# controller.net
KiCad netlist of a schematic drawn in EAGLE
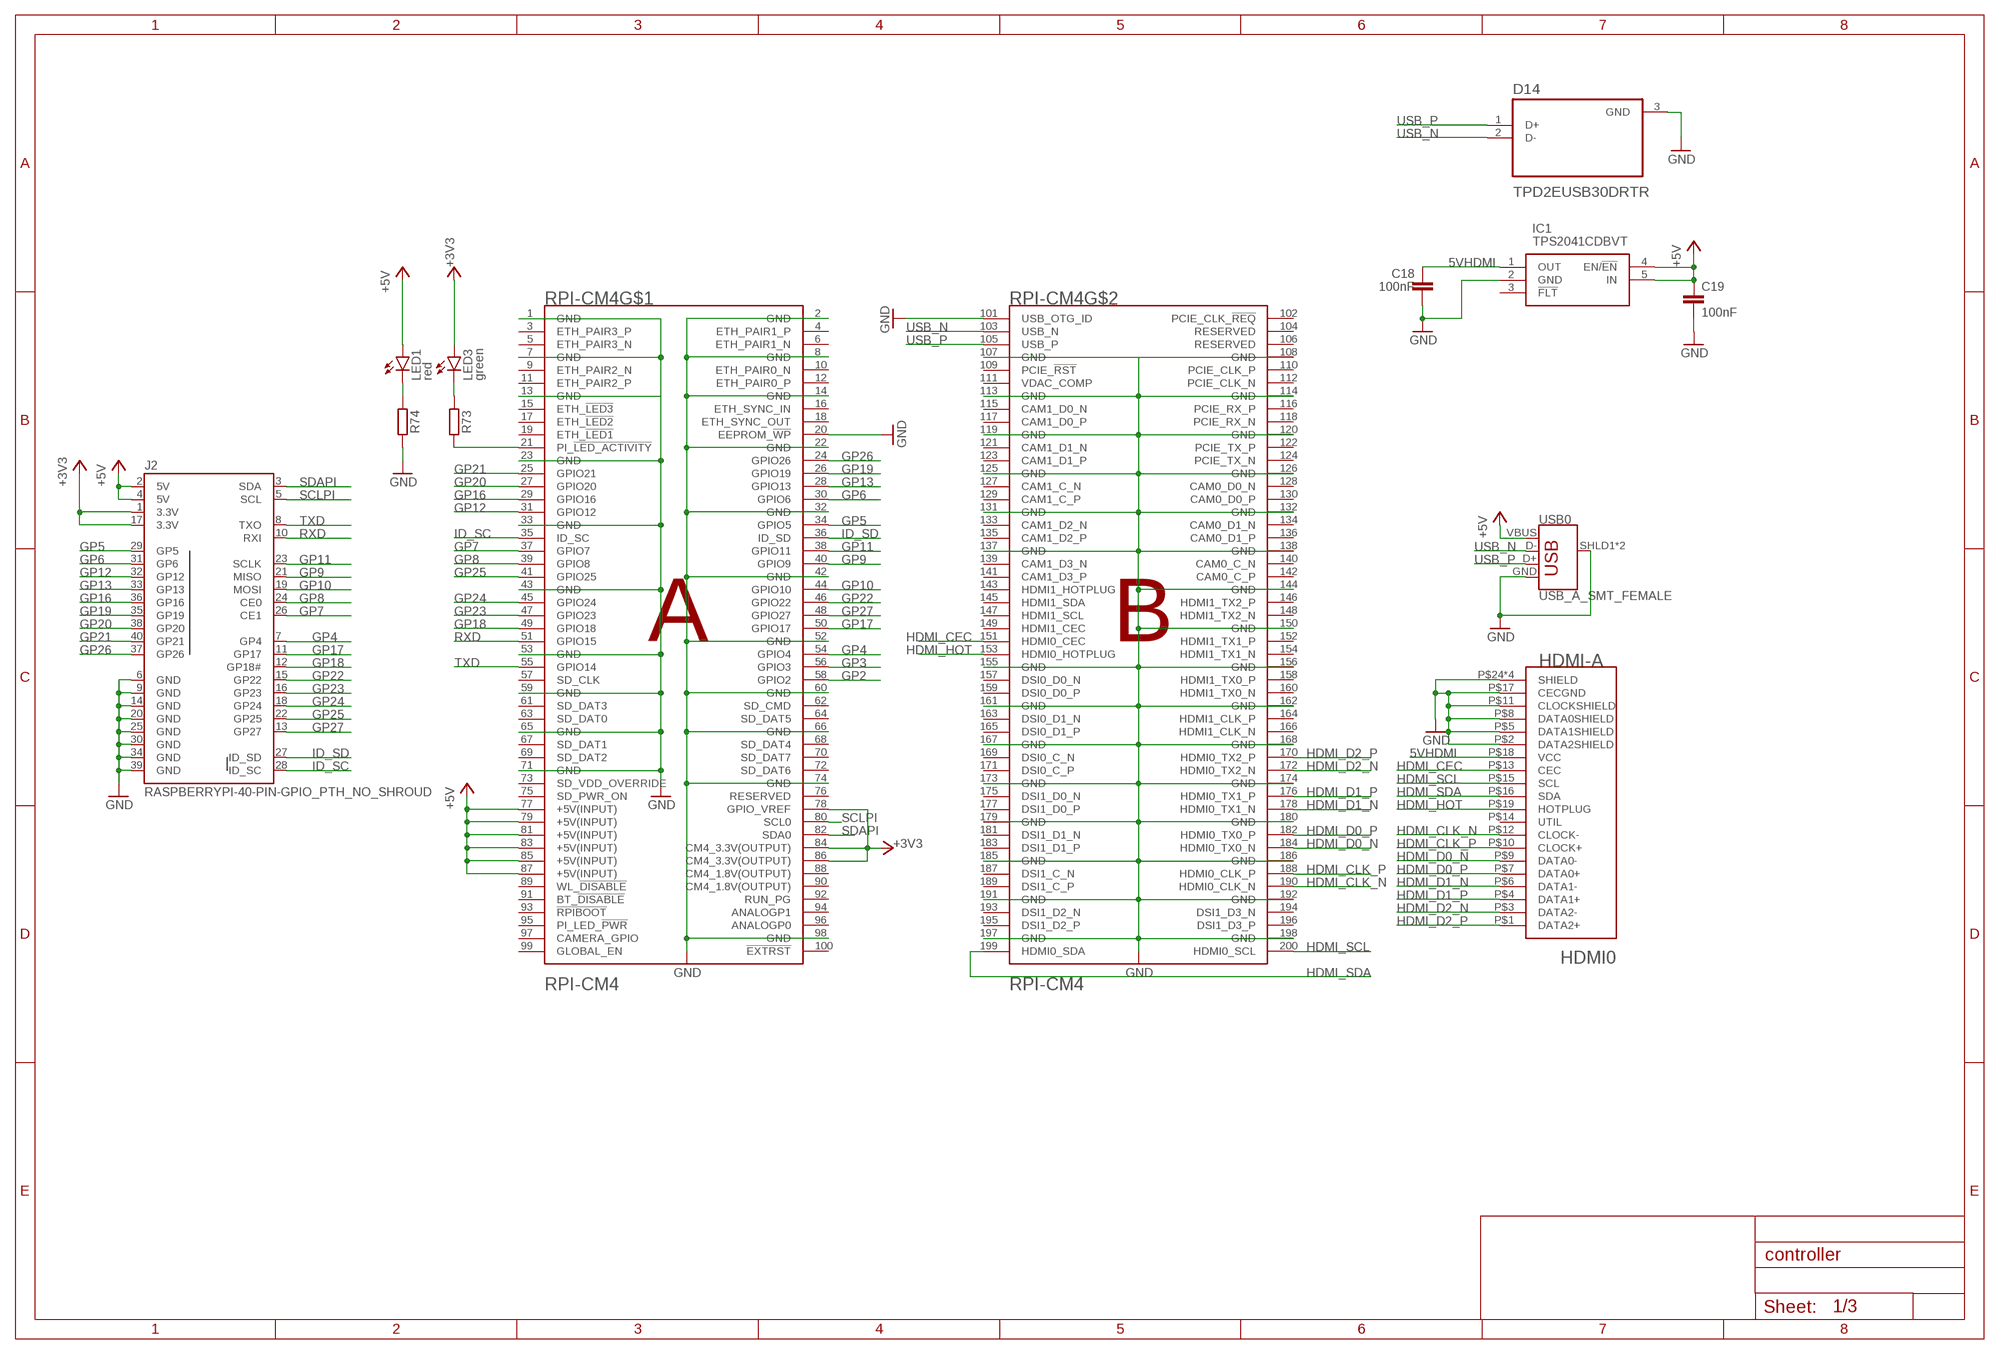
[diagram p0: schematic, sheet 1]
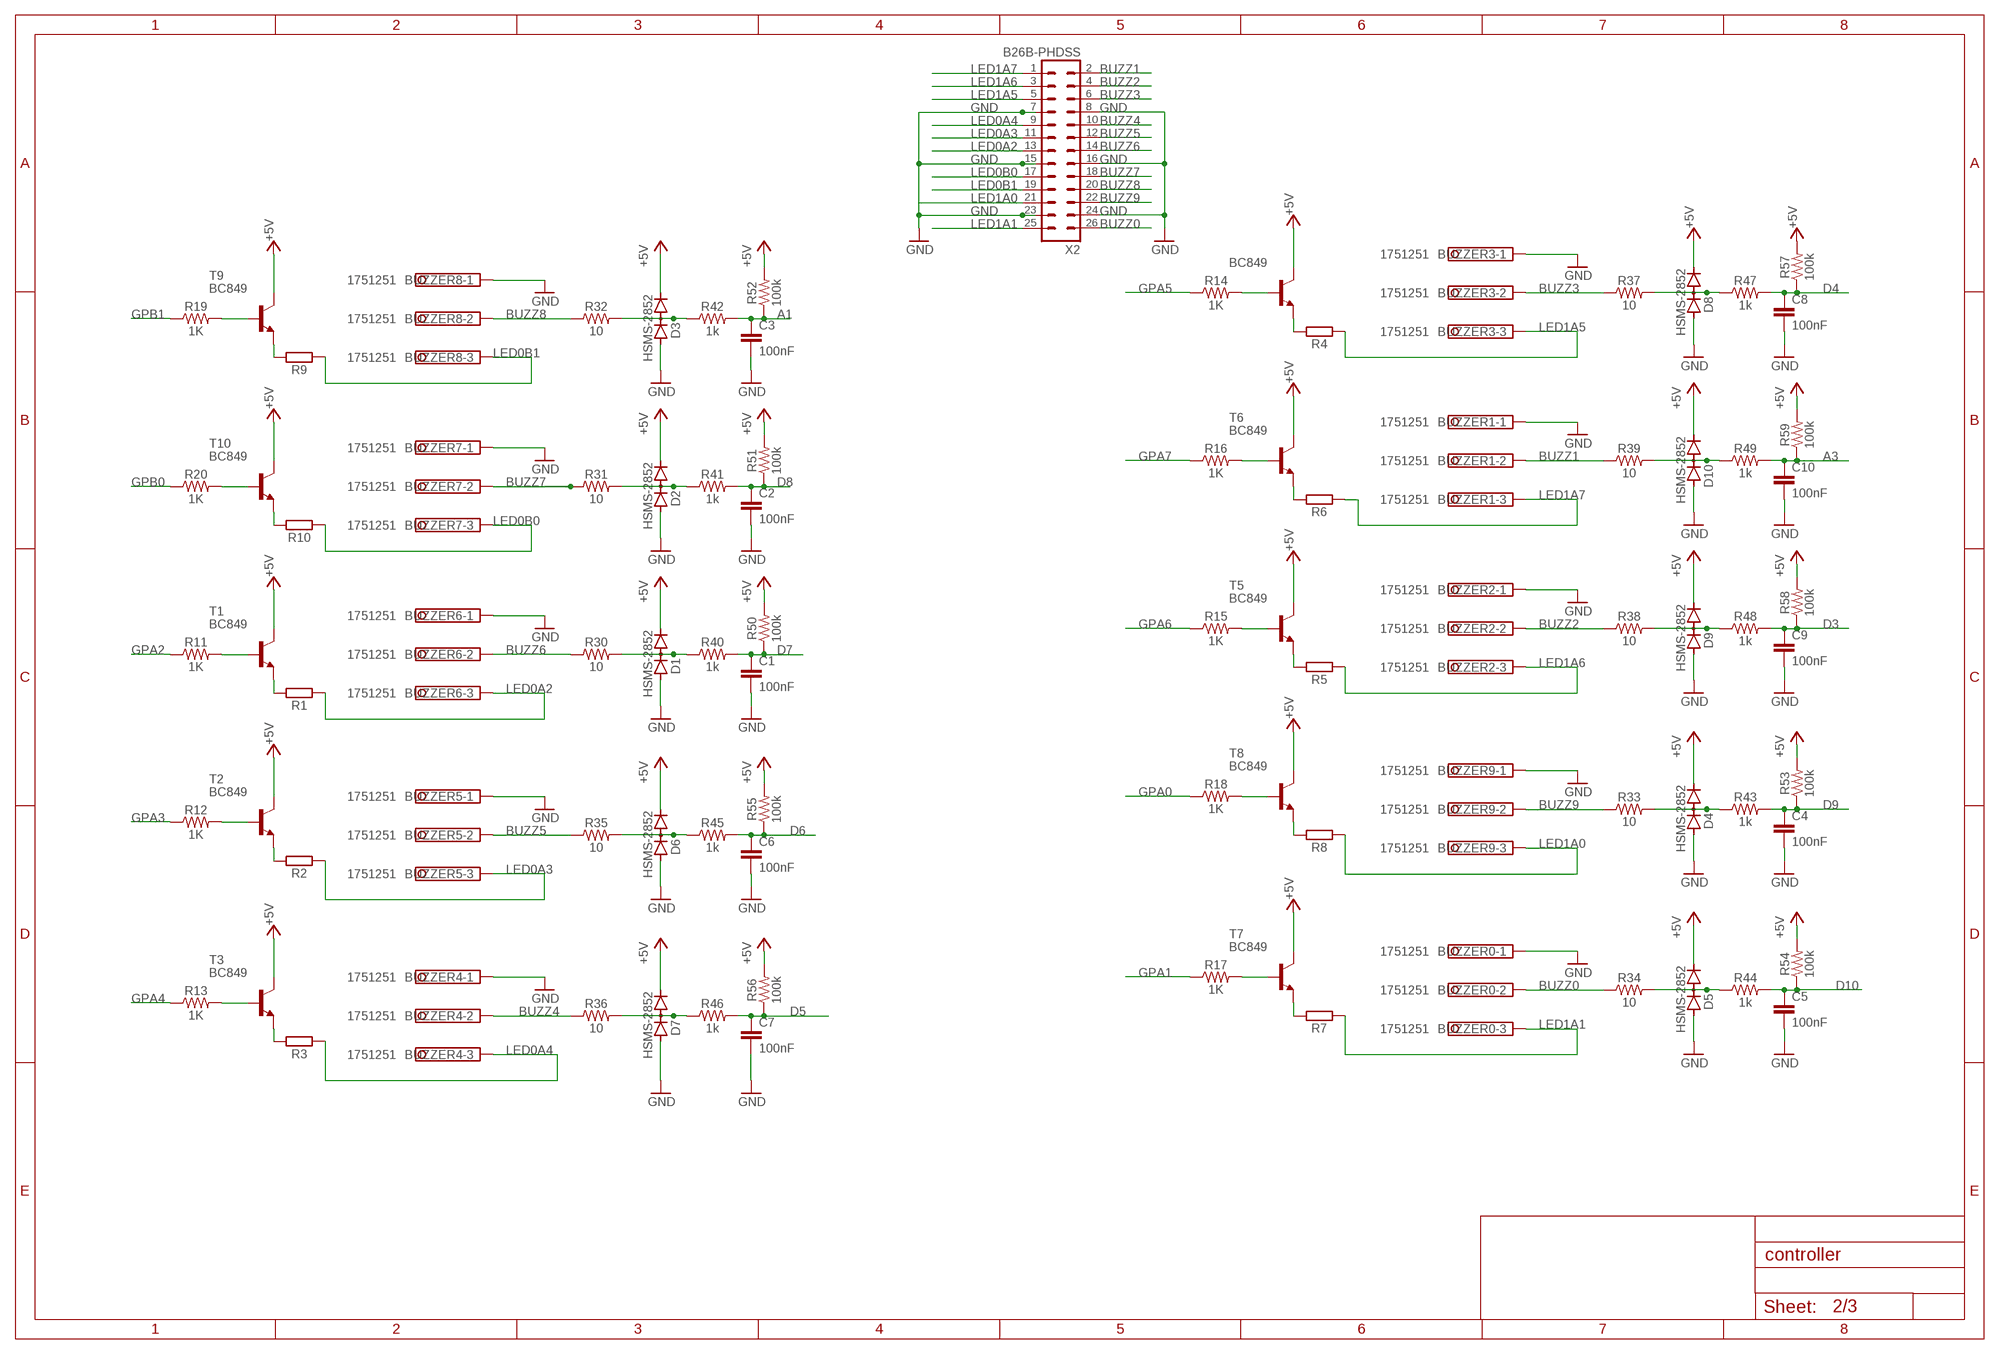
[diagram p1: schematic, sheet 2]
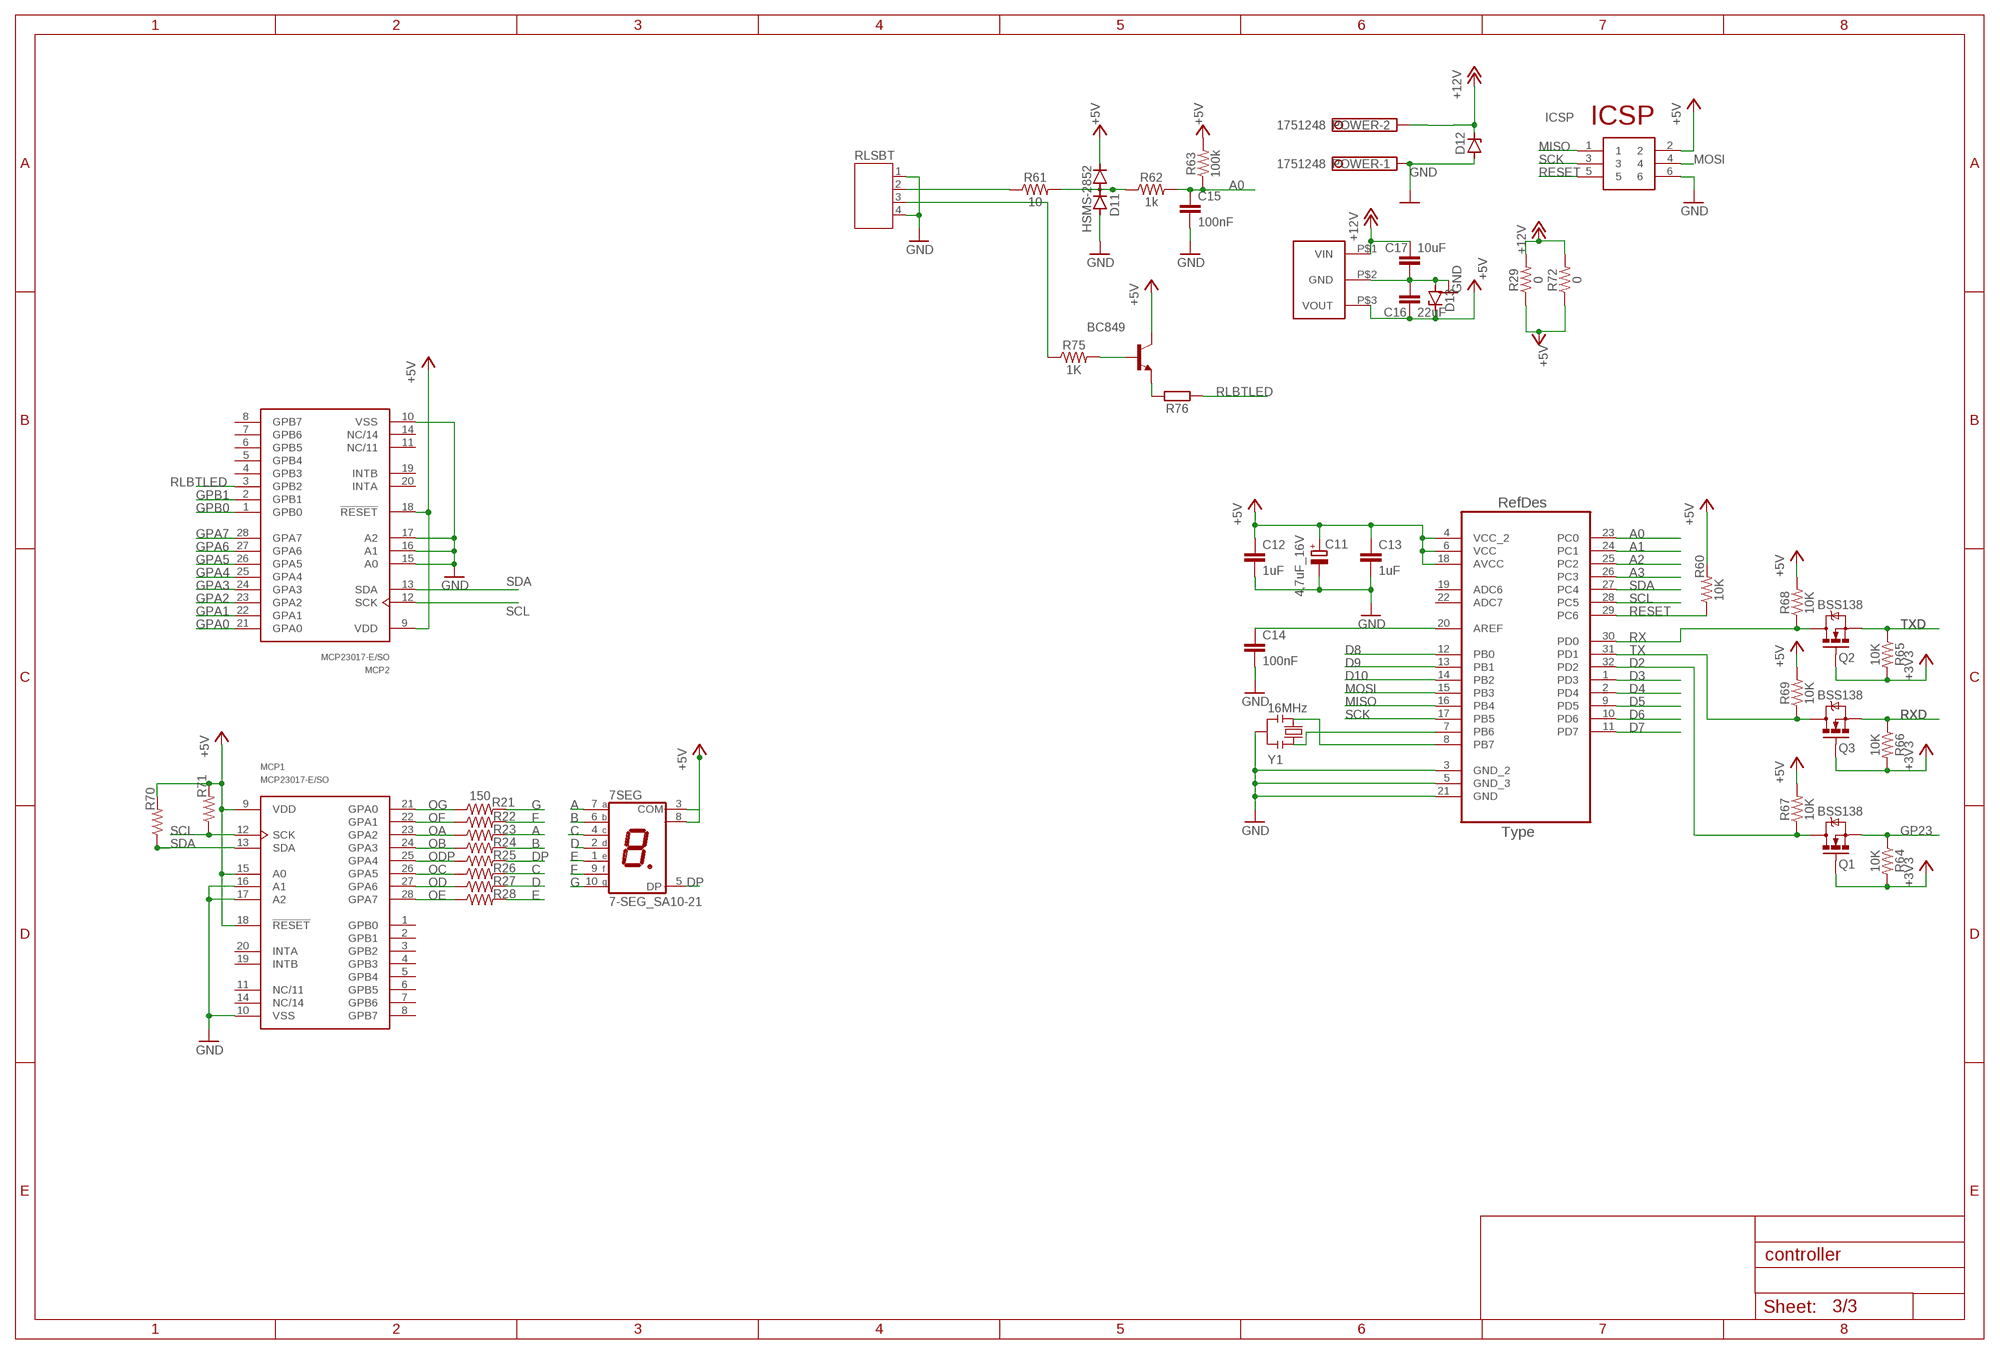
[diagram p2: schematic, sheet 3]

(export (version "E")
  (design (tool "Eeschema 10.0.6"))
  (components
    (comp (ref "7SEG")
      (value "7-SEG_SA10-21")
      (footprint "eagle-import:SA10-21")
      (libsource (lib "eagle-import") (part "7-SEG_SA10-21"))
    )
    (comp (ref "C11")
      (value "4,7uF_16V")
      (footprint "eagle-import:TAN-A")
      (fields (field (name "PART_NUMBER") "TAJA475MO16RNJ"))
      (libsource (lib "eagle-import") (part "0833_TAJA475MO16RNJ"))
    )
    (comp (ref "C12")
      (value "1uF")
      (footprint "eagle-import:C0603-ROUND")
      (fields (field (name "PART_NUMBER") "1uF_0603/GRM188R61E105KA12D"))
      (libsource (lib "eagle-import") (part "0006_1UF_0603/GRM188R61E105KA12D"))
    )
    (comp (ref "C13")
      (value "1uF")
      (footprint "eagle-import:C0603-ROUND")
      (fields (field (name "PART_NUMBER") "1uF_0603/GRM188R61E105KA12D"))
      (libsource (lib "eagle-import") (part "0006_1UF_0603/GRM188R61E105KA12D"))
    )
    (comp (ref "C14")
      (value "100nF")
      (footprint "eagle-import:C0603-ROUND")
      (fields (field (name "PART_NUMBER") "cl10b104kbnc"))
      (libsource (lib "eagle-import") (part "0015_100NF_0603"))
    )
    (comp (ref "C15")
      (value "100nF")
      (footprint "eagle-import:C0805")
      (libsource (lib "eagle-import") (part "C-EUC0805"))
    )
    (comp (ref "C16")
      (value "22uF")
      (footprint "eagle-import:C0805")
      (libsource (lib "eagle-import") (part "C-EUC0805"))
    )
    (comp (ref "C17")
      (value "10uF")
      (footprint "eagle-import:C0805")
      (libsource (lib "eagle-import") (part "C-EUC0805"))
    )
    (comp (ref "D11")
      (value "HSMS-2852")
      (footprint "eagle-import:SOT23")
      (libsource (lib "eagle-import") (part "HSMS-2852"))
    )
    (comp (ref "D12")
      (value "ZENER-DIODESMB")
      (footprint "eagle-import:SMB")
      (libsource (lib "eagle-import") (part "ZENER-DIODESMB"))
    )
    (comp (ref "D13")
      (value "ZENER-DIODESMB")
      (footprint "eagle-import:SMB")
      (libsource (lib "eagle-import") (part "ZENER-DIODESMB"))
    )
    (comp (ref "ICSP")
      (value "61200621621")
      (footprint "eagle-import:SHDR6W64P254_2X3_1528X910X910P")
      (fields (field (name "MOUSER_PART_NUMBER") "710-61200621621"))
      (libsource (lib "eagle-import") (part "61200621621"))
    )
    (comp (ref "MCP1")
      (value "MCP23017-E/SO")
      (footprint "eagle-import:SOIC28")
      (libsource (lib "eagle-import") (part "MCP23017-E/SO"))
    )
    (comp (ref "MCP2")
      (value "MCP23017-E/SO")
      (footprint "eagle-import:SOIC28")
      (libsource (lib "eagle-import") (part "MCP23017-E/SO"))
    )
    (comp (ref "POWER")
      (value "1751248")
      (footprint "eagle-import:1751248")
      (libsource (lib "eagle-import") (part "1751248"))
    )
    (comp (ref "Q1")
      (value "BSS138")
      (footprint "eagle-import:SOT23-3")
      (libsource (lib "eagle-import") (part "MOSFET-NCHANNELSMD"))
    )
    (comp (ref "Q2")
      (value "BSS138")
      (footprint "eagle-import:SOT23-3")
      (libsource (lib "eagle-import") (part "MOSFET-NCHANNELSMD"))
    )
    (comp (ref "Q3")
      (value "BSS138")
      (footprint "eagle-import:SOT23-3")
      (libsource (lib "eagle-import") (part "MOSFET-NCHANNELSMD"))
    )
    (comp (ref "R21")
      (value "150")
      (footprint "eagle-import:0805")
      (libsource (lib "eagle-import") (part "RESISTOR0805"))
    )
    (comp (ref "R22")
      (value "150")
      (footprint "eagle-import:0805")
      (libsource (lib "eagle-import") (part "RESISTOR0805"))
    )
    (comp (ref "R23")
      (value "150")
      (footprint "eagle-import:0805")
      (libsource (lib "eagle-import") (part "RESISTOR0805"))
    )
    (comp (ref "R24")
      (value "150")
      (footprint "eagle-import:0805")
      (libsource (lib "eagle-import") (part "RESISTOR0805"))
    )
    (comp (ref "R25")
      (value "150")
      (footprint "eagle-import:0805")
      (libsource (lib "eagle-import") (part "RESISTOR0805"))
    )
    (comp (ref "R26")
      (value "150")
      (footprint "eagle-import:0805")
      (libsource (lib "eagle-import") (part "RESISTOR0805"))
    )
    (comp (ref "R27")
      (value "150")
      (footprint "eagle-import:0805")
      (libsource (lib "eagle-import") (part "RESISTOR0805"))
    )
    (comp (ref "R28")
      (value "150")
      (footprint "eagle-import:0805")
      (libsource (lib "eagle-import") (part "RESISTOR0805"))
    )
    (comp (ref "R29")
      (value "0")
      (footprint "eagle-import:0805")
      (libsource (lib "eagle-import") (part "RESISTOR0805"))
    )
    (comp (ref "R60")
      (value "10K")
      (footprint "eagle-import:0805")
      (libsource (lib "eagle-import") (part "RESISTOR0805"))
    )
    (comp (ref "R61")
      (value "10")
      (footprint "eagle-import:0805")
      (libsource (lib "eagle-import") (part "RESISTOR0805"))
    )
    (comp (ref "R62")
      (value "1k")
      (footprint "eagle-import:0805")
      (libsource (lib "eagle-import") (part "RESISTOR0805"))
    )
    (comp (ref "R63")
      (value "100k")
      (footprint "eagle-import:0805")
      (libsource (lib "eagle-import") (part "RESISTOR0805"))
    )
    (comp (ref "R64")
      (value "10K")
      (footprint "eagle-import:0805")
      (libsource (lib "eagle-import") (part "RESISTOR0805"))
    )
    (comp (ref "R65")
      (value "10K")
      (footprint "eagle-import:0805")
      (libsource (lib "eagle-import") (part "RESISTOR0805"))
    )
    (comp (ref "R66")
      (value "10K")
      (footprint "eagle-import:0805")
      (libsource (lib "eagle-import") (part "RESISTOR0805"))
    )
    (comp (ref "R67")
      (value "10K")
      (footprint "eagle-import:0805")
      (libsource (lib "eagle-import") (part "RESISTOR0805"))
    )
    (comp (ref "R68")
      (value "10K")
      (footprint "eagle-import:0805")
      (libsource (lib "eagle-import") (part "RESISTOR0805"))
    )
    (comp (ref "R69")
      (value "10K")
      (footprint "eagle-import:0805")
      (libsource (lib "eagle-import") (part "RESISTOR0805"))
    )
    (comp (ref "R70")
      (value "RESISTOR0805")
      (footprint "eagle-import:0805")
      (libsource (lib "eagle-import") (part "RESISTOR0805"))
    )
    (comp (ref "R71")
      (value "RESISTOR0805")
      (footprint "eagle-import:0805")
      (libsource (lib "eagle-import") (part "RESISTOR0805"))
    )
    (comp (ref "R72")
      (value "0")
      (footprint "eagle-import:0805")
      (libsource (lib "eagle-import") (part "RESISTOR0805"))
    )
    (comp (ref "R75")
      (value "1K")
      (footprint "eagle-import:0805")
      (libsource (lib "eagle-import") (part "RESISTOR0805"))
    )
    (comp (ref "R76")
      (value "50")
      (footprint "eagle-import:R2512")
      (libsource (lib "eagle-import") (part "R-EU_R2512"))
    )
    (comp (ref "RLSBT")
      (value "JST-PH4")
      (footprint "eagle-import:JST-PH4")
      (libsource (lib "eagle-import") (part "JST-PH4"))
    )
    (comp (ref "T11")
      (value "BC849")
      (footprint "eagle-import:SOT23")
      (libsource (lib "eagle-import") (part "BC849"))
    )
    (comp (ref "U$5")
      (value "GAPTECCLC78")
      (footprint "eagle-import:GAPTECLC78")
      (libsource (lib "eagle-import") (part "GAPTECCLC78"))
    )
    (comp (ref "U1")
      (value "ATMEGA328P-AU")
      (footprint "eagle-import:QFP80P900X900X120-32N")
      (libsource (lib "eagle-import") (part "ATMEGA328P-AU"))
    )
    (comp (ref "Y1")
      (value "16MHz")
      (footprint "eagle-import:RESONATOR")
      (fields (field (name "PART_NUMBER") "CSTCE16M0V53-R0"))
      (libsource (lib "eagle-import") (part "0011_CSTCE16M0V53-R0"))
    )
    (comp (ref "C18")
      (value "100nF")
      (footprint "eagle-import:C0805")
      (libsource (lib "eagle-import") (part "C-EUC0805"))
    )
    (comp (ref "C19")
      (value "100nF")
      (footprint "eagle-import:C0805")
      (libsource (lib "eagle-import") (part "C-EUC0805"))
    )
    (comp (ref "D14")
      (value "TPD2EUSB30DRTR")
      (footprint "eagle-import:SOTFL35P100X50-3N")
      (fields (field (name "DIGI-KEY_PART_NUMBER") "296-25509-1-ND") (field (name "MF") "Texas Instruments"))
      (libsource (lib "eagle-import") (part "TPD2EUSB30DRTR"))
    )
    (comp (ref "HDMI0")
      (value "HDMI-A")
      (footprint "eagle-import:HDMI_A")
      (libsource (lib "eagle-import") (part "HDMI-A"))
    )
    (comp (ref "IC1")
      (value "TPS2041CDBVT")
      (footprint "eagle-import:SOT95P280X145-5N")
      (fields (field (name "MOUSER_PART_NUMBER") "595-TPS2041CDBVT"))
      (libsource (lib "eagle-import") (part "TPS2041CDBVT"))
    )
    (comp (ref "J2")
      (value "RASPBERRYPI-40-PIN-GPIO_PTH_NO_SHROUD")
      (footprint "eagle-import:2X20")
      (libsource (lib "eagle-import") (part "RASPBERRYPI-40-PIN-GPIO_PTH_NO_SHROUD"))
    )
    (comp (ref "LED1")
      (value "red")
      (footprint "eagle-import:CHIP-LED0805")
      (libsource (lib "eagle-import") (part "LEDCHIP-LED0805"))
    )
    (comp (ref "LED3")
      (value "green")
      (footprint "eagle-import:CHIP-LED0805")
      (libsource (lib "eagle-import") (part "LEDCHIP-LED0805"))
    )
    (comp (ref "R73")
      (value "1k")
      (footprint "eagle-import:R0805")
      (libsource (lib "eagle-import") (part "R-EU_R0805"))
    )
    (comp (ref "R74")
      (value "1k")
      (footprint "eagle-import:R0805")
      (libsource (lib "eagle-import") (part "R-EU_R0805"))
    )
    (comp (ref "RPI-CM4")
      (value "RPI-CM4")
      (footprint "eagle-import:RPI-CM4")
      (libsource (lib "eagle-import") (part "RPI-CM4"))
    )
    (comp (ref "USB0")
      (value "USB_A_SMT_FEMALE")
      (footprint "eagle-import:USB-A-S-SILK-FEMALE")
      (libsource (lib "eagle-import") (part "USB_A_SMT_FEMALE"))
    )
    (comp (ref "BUZZER0")
      (value "1751251")
      (footprint "eagle-import:1751251")
      (libsource (lib "eagle-import") (part "1751251"))
    )
    (comp (ref "BUZZER1")
      (value "1751251")
      (footprint "eagle-import:1751251")
      (libsource (lib "eagle-import") (part "1751251"))
    )
    (comp (ref "BUZZER2")
      (value "1751251")
      (footprint "eagle-import:1751251")
      (libsource (lib "eagle-import") (part "1751251"))
    )
    (comp (ref "BUZZER3")
      (value "1751251")
      (footprint "eagle-import:1751251")
      (libsource (lib "eagle-import") (part "1751251"))
    )
    (comp (ref "BUZZER4")
      (value "1751251")
      (footprint "eagle-import:1751251")
      (libsource (lib "eagle-import") (part "1751251"))
    )
    (comp (ref "BUZZER5")
      (value "1751251")
      (footprint "eagle-import:1751251")
      (libsource (lib "eagle-import") (part "1751251"))
    )
    (comp (ref "BUZZER6")
      (value "1751251")
      (footprint "eagle-import:1751251")
      (libsource (lib "eagle-import") (part "1751251"))
    )
    (comp (ref "BUZZER7")
      (value "1751251")
      (footprint "eagle-import:1751251")
      (libsource (lib "eagle-import") (part "1751251"))
    )
    (comp (ref "BUZZER8")
      (value "1751251")
      (footprint "eagle-import:1751251")
      (libsource (lib "eagle-import") (part "1751251"))
    )
    (comp (ref "BUZZER9")
      (value "1751251")
      (footprint "eagle-import:1751251")
      (libsource (lib "eagle-import") (part "1751251"))
    )
    (comp (ref "C1")
      (value "100nF")
      (footprint "eagle-import:C0805")
      (libsource (lib "eagle-import") (part "C-EUC0805"))
    )
    (comp (ref "C2")
      (value "100nF")
      (footprint "eagle-import:C0805")
      (libsource (lib "eagle-import") (part "C-EUC0805"))
    )
    (comp (ref "C3")
      (value "100nF")
      (footprint "eagle-import:C0805")
      (libsource (lib "eagle-import") (part "C-EUC0805"))
    )
    (comp (ref "C4")
      (value "100nF")
      (footprint "eagle-import:C0805")
      (libsource (lib "eagle-import") (part "C-EUC0805"))
    )
    (comp (ref "C5")
      (value "100nF")
      (footprint "eagle-import:C0805")
      (libsource (lib "eagle-import") (part "C-EUC0805"))
    )
    (comp (ref "C6")
      (value "100nF")
      (footprint "eagle-import:C0805")
      (libsource (lib "eagle-import") (part "C-EUC0805"))
    )
    (comp (ref "C7")
      (value "100nF")
      (footprint "eagle-import:C0805")
      (libsource (lib "eagle-import") (part "C-EUC0805"))
    )
    (comp (ref "C8")
      (value "100nF")
      (footprint "eagle-import:C0805")
      (libsource (lib "eagle-import") (part "C-EUC0805"))
    )
    (comp (ref "C9")
      (value "100nF")
      (footprint "eagle-import:C0805")
      (libsource (lib "eagle-import") (part "C-EUC0805"))
    )
    (comp (ref "C10")
      (value "100nF")
      (footprint "eagle-import:C0805")
      (libsource (lib "eagle-import") (part "C-EUC0805"))
    )
    (comp (ref "D1")
      (value "HSMS-2852")
      (footprint "eagle-import:SOT23")
      (libsource (lib "eagle-import") (part "HSMS-2852"))
    )
    (comp (ref "D2")
      (value "HSMS-2852")
      (footprint "eagle-import:SOT23")
      (libsource (lib "eagle-import") (part "HSMS-2852"))
    )
    (comp (ref "D3")
      (value "HSMS-2852")
      (footprint "eagle-import:SOT23")
      (libsource (lib "eagle-import") (part "HSMS-2852"))
    )
    (comp (ref "D4")
      (value "HSMS-2852")
      (footprint "eagle-import:SOT23")
      (libsource (lib "eagle-import") (part "HSMS-2852"))
    )
    (comp (ref "D5")
      (value "HSMS-2852")
      (footprint "eagle-import:SOT23")
      (libsource (lib "eagle-import") (part "HSMS-2852"))
    )
    (comp (ref "D6")
      (value "HSMS-2852")
      (footprint "eagle-import:SOT23")
      (libsource (lib "eagle-import") (part "HSMS-2852"))
    )
    (comp (ref "D7")
      (value "HSMS-2852")
      (footprint "eagle-import:SOT23")
      (libsource (lib "eagle-import") (part "HSMS-2852"))
    )
    (comp (ref "D8")
      (value "HSMS-2852")
      (footprint "eagle-import:SOT23")
      (libsource (lib "eagle-import") (part "HSMS-2852"))
    )
    (comp (ref "D9")
      (value "HSMS-2852")
      (footprint "eagle-import:SOT23")
      (libsource (lib "eagle-import") (part "HSMS-2852"))
    )
    (comp (ref "D10")
      (value "HSMS-2852")
      (footprint "eagle-import:SOT23")
      (libsource (lib "eagle-import") (part "HSMS-2852"))
    )
    (comp (ref "R1")
      (value "50")
      (footprint "eagle-import:R2512")
      (libsource (lib "eagle-import") (part "R-EU_R2512"))
    )
    (comp (ref "R2")
      (value "50")
      (footprint "eagle-import:R2512")
      (libsource (lib "eagle-import") (part "R-EU_R2512"))
    )
    (comp (ref "R3")
      (value "50")
      (footprint "eagle-import:R2512")
      (libsource (lib "eagle-import") (part "R-EU_R2512"))
    )
    (comp (ref "R4")
      (value "50")
      (footprint "eagle-import:R2512")
      (libsource (lib "eagle-import") (part "R-EU_R2512"))
    )
    (comp (ref "R5")
      (value "50")
      (footprint "eagle-import:R2512")
      (libsource (lib "eagle-import") (part "R-EU_R2512"))
    )
    (comp (ref "R6")
      (value "50")
      (footprint "eagle-import:R2512")
      (libsource (lib "eagle-import") (part "R-EU_R2512"))
    )
    (comp (ref "R7")
      (value "50")
      (footprint "eagle-import:R2512")
      (libsource (lib "eagle-import") (part "R-EU_R2512"))
    )
    (comp (ref "R8")
      (value "50")
      (footprint "eagle-import:R2512")
      (libsource (lib "eagle-import") (part "R-EU_R2512"))
    )
    (comp (ref "R9")
      (value "50")
      (footprint "eagle-import:R2512")
      (libsource (lib "eagle-import") (part "R-EU_R2512"))
    )
    (comp (ref "R10")
      (value "50")
      (footprint "eagle-import:R2512")
      (libsource (lib "eagle-import") (part "R-EU_R2512"))
    )
    (comp (ref "R11")
      (value "1K")
      (footprint "eagle-import:0805")
      (libsource (lib "eagle-import") (part "RESISTOR0805"))
    )
    (comp (ref "R12")
      (value "1K")
      (footprint "eagle-import:0805")
      (libsource (lib "eagle-import") (part "RESISTOR0805"))
    )
    (comp (ref "R13")
      (value "1K")
      (footprint "eagle-import:0805")
      (libsource (lib "eagle-import") (part "RESISTOR0805"))
    )
    (comp (ref "R14")
      (value "1K")
      (footprint "eagle-import:0805")
      (libsource (lib "eagle-import") (part "RESISTOR0805"))
    )
    (comp (ref "R15")
      (value "1K")
      (footprint "eagle-import:0805")
      (libsource (lib "eagle-import") (part "RESISTOR0805"))
    )
    (comp (ref "R16")
      (value "1K")
      (footprint "eagle-import:0805")
      (libsource (lib "eagle-import") (part "RESISTOR0805"))
    )
    (comp (ref "R17")
      (value "1K")
      (footprint "eagle-import:0805")
      (libsource (lib "eagle-import") (part "RESISTOR0805"))
    )
    (comp (ref "R18")
      (value "1K")
      (footprint "eagle-import:0805")
      (libsource (lib "eagle-import") (part "RESISTOR0805"))
    )
    (comp (ref "R19")
      (value "1K")
      (footprint "eagle-import:0805")
      (libsource (lib "eagle-import") (part "RESISTOR0805"))
    )
    (comp (ref "R20")
      (value "1K")
      (footprint "eagle-import:0805")
      (libsource (lib "eagle-import") (part "RESISTOR0805"))
    )
    (comp (ref "R30")
      (value "10")
      (footprint "eagle-import:0805")
      (libsource (lib "eagle-import") (part "RESISTOR0805"))
    )
    (comp (ref "R31")
      (value "10")
      (footprint "eagle-import:0805")
      (libsource (lib "eagle-import") (part "RESISTOR0805"))
    )
    (comp (ref "R32")
      (value "10")
      (footprint "eagle-import:0805")
      (libsource (lib "eagle-import") (part "RESISTOR0805"))
    )
    (comp (ref "R33")
      (value "10")
      (footprint "eagle-import:0805")
      (libsource (lib "eagle-import") (part "RESISTOR0805"))
    )
    (comp (ref "R34")
      (value "10")
      (footprint "eagle-import:0805")
      (libsource (lib "eagle-import") (part "RESISTOR0805"))
    )
    (comp (ref "R35")
      (value "10")
      (footprint "eagle-import:0805")
      (libsource (lib "eagle-import") (part "RESISTOR0805"))
    )
    (comp (ref "R36")
      (value "10")
      (footprint "eagle-import:0805")
      (libsource (lib "eagle-import") (part "RESISTOR0805"))
    )
    (comp (ref "R37")
      (value "10")
      (footprint "eagle-import:0805")
      (libsource (lib "eagle-import") (part "RESISTOR0805"))
    )
    (comp (ref "R38")
      (value "10")
      (footprint "eagle-import:0805")
      (libsource (lib "eagle-import") (part "RESISTOR0805"))
    )
    (comp (ref "R39")
      (value "10")
      (footprint "eagle-import:0805")
      (libsource (lib "eagle-import") (part "RESISTOR0805"))
    )
    (comp (ref "R40")
      (value "1k")
      (footprint "eagle-import:0805")
      (libsource (lib "eagle-import") (part "RESISTOR0805"))
    )
    (comp (ref "R41")
      (value "1k")
      (footprint "eagle-import:0805")
      (libsource (lib "eagle-import") (part "RESISTOR0805"))
    )
    (comp (ref "R42")
      (value "1k")
      (footprint "eagle-import:0805")
      (libsource (lib "eagle-import") (part "RESISTOR0805"))
    )
    (comp (ref "R43")
      (value "1k")
      (footprint "eagle-import:0805")
      (libsource (lib "eagle-import") (part "RESISTOR0805"))
    )
    (comp (ref "R44")
      (value "1k")
      (footprint "eagle-import:0805")
      (libsource (lib "eagle-import") (part "RESISTOR0805"))
    )
    (comp (ref "R45")
      (value "1k")
      (footprint "eagle-import:0805")
      (libsource (lib "eagle-import") (part "RESISTOR0805"))
    )
    (comp (ref "R46")
      (value "1k")
      (footprint "eagle-import:0805")
      (libsource (lib "eagle-import") (part "RESISTOR0805"))
    )
    (comp (ref "R47")
      (value "1k")
      (footprint "eagle-import:0805")
      (libsource (lib "eagle-import") (part "RESISTOR0805"))
    )
    (comp (ref "R48")
      (value "1k")
      (footprint "eagle-import:0805")
      (libsource (lib "eagle-import") (part "RESISTOR0805"))
    )
    (comp (ref "R49")
      (value "1k")
      (footprint "eagle-import:0805")
      (libsource (lib "eagle-import") (part "RESISTOR0805"))
    )
    (comp (ref "R50")
      (value "100k")
      (footprint "eagle-import:0805")
      (libsource (lib "eagle-import") (part "RESISTOR0805"))
    )
    (comp (ref "R51")
      (value "100k")
      (footprint "eagle-import:0805")
      (libsource (lib "eagle-import") (part "RESISTOR0805"))
    )
    (comp (ref "R52")
      (value "100k")
      (footprint "eagle-import:0805")
      (libsource (lib "eagle-import") (part "RESISTOR0805"))
    )
    (comp (ref "R53")
      (value "100k")
      (footprint "eagle-import:0805")
      (libsource (lib "eagle-import") (part "RESISTOR0805"))
    )
    (comp (ref "R54")
      (value "100k")
      (footprint "eagle-import:0805")
      (libsource (lib "eagle-import") (part "RESISTOR0805"))
    )
    (comp (ref "R55")
      (value "100k")
      (footprint "eagle-import:0805")
      (libsource (lib "eagle-import") (part "RESISTOR0805"))
    )
    (comp (ref "R56")
      (value "100k")
      (footprint "eagle-import:0805")
      (libsource (lib "eagle-import") (part "RESISTOR0805"))
    )
    (comp (ref "R57")
      (value "100k")
      (footprint "eagle-import:0805")
      (libsource (lib "eagle-import") (part "RESISTOR0805"))
    )
    (comp (ref "R58")
      (value "100k")
      (footprint "eagle-import:0805")
      (libsource (lib "eagle-import") (part "RESISTOR0805"))
    )
    (comp (ref "R59")
      (value "100k")
      (footprint "eagle-import:0805")
      (libsource (lib "eagle-import") (part "RESISTOR0805"))
    )
    (comp (ref "T1")
      (value "BC849")
      (footprint "eagle-import:SOT23")
      (libsource (lib "eagle-import") (part "BC849"))
    )
    (comp (ref "T2")
      (value "BC849")
      (footprint "eagle-import:SOT23")
      (libsource (lib "eagle-import") (part "BC849"))
    )
    (comp (ref "T3")
      (value "BC849")
      (footprint "eagle-import:SOT23")
      (libsource (lib "eagle-import") (part "BC849"))
    )
    (comp (ref "T4")
      (value "BC849")
      (footprint "eagle-import:SOT23")
      (libsource (lib "eagle-import") (part "BC849"))
    )
    (comp (ref "T5")
      (value "BC849")
      (footprint "eagle-import:SOT23")
      (libsource (lib "eagle-import") (part "BC849"))
    )
    (comp (ref "T6")
      (value "BC849")
      (footprint "eagle-import:SOT23")
      (libsource (lib "eagle-import") (part "BC849"))
    )
    (comp (ref "T7")
      (value "BC849")
      (footprint "eagle-import:SOT23")
      (libsource (lib "eagle-import") (part "BC849"))
    )
    (comp (ref "T8")
      (value "BC849")
      (footprint "eagle-import:SOT23")
      (libsource (lib "eagle-import") (part "BC849"))
    )
    (comp (ref "T9")
      (value "BC849")
      (footprint "eagle-import:SOT23")
      (libsource (lib "eagle-import") (part "BC849"))
    )
    (comp (ref "T10")
      (value "BC849")
      (footprint "eagle-import:SOT23")
      (libsource (lib "eagle-import") (part "BC849"))
    )
    (comp (ref "X2")
      (value "B26B-PHDSS")
      (footprint "eagle-import:B26B-PHDSS")
      (libsource (lib "eagle-import") (part "B26B-PHDSS"))
    )
  )
  (nets
    (net (code "1") (name "+3V3") (class "Default")
      (node (ref "J2") (pin "1") (pinfunction "3.3V_1") (pintype "power_in"))
      (node (ref "J2") (pin "17") (pinfunction "3.3V_17") (pintype "power_in"))
      (node (ref "LED3") (pin "A") (pinfunction "A_A") (pintype "passive"))
      (node (ref "Q1") (pin "1") (pinfunction "G_1") (pintype "passive"))
      (node (ref "Q2") (pin "1") (pinfunction "G_1") (pintype "passive"))
      (node (ref "Q3") (pin "1") (pinfunction "G_1") (pintype "passive"))
      (node (ref "R64") (pin "2") (pinfunction "2_2") (pintype "passive"))
      (node (ref "R65") (pin "2") (pinfunction "2_2") (pintype "passive"))
      (node (ref "R66") (pin "2") (pinfunction "2_2") (pintype "passive"))
      (node (ref "RPI-CM4") (pin "78") (pinfunction "GPIO_VREF_78") (pintype "passive"))
      (node (ref "RPI-CM4") (pin "84") (pinfunction "CM4_3.3V(OUTPUT)_84") (pintype "passive"))
      (node (ref "RPI-CM4") (pin "86") (pinfunction "CM4_3.3V(OUTPUT)_86") (pintype "passive"))
    )
    (net (code "2") (name "+5V") (class "Default")
      (node (ref "7SEG") (pin "3") (pinfunction "COM_3") (pintype "passive"))
      (node (ref "7SEG") (pin "8") (pinfunction "COM_8") (pintype "passive"))
      (node (ref "C11") (pin "1") (pinfunction "+_1") (pintype "passive"))
      (node (ref "C12") (pin "1") (pinfunction "1_1") (pintype "passive"))
      (node (ref "C13") (pin "1") (pinfunction "1_1") (pintype "passive"))
      (node (ref "C16") (pin "2") (pinfunction "2_2") (pintype "passive"))
      (node (ref "C19") (pin "1") (pinfunction "1_1") (pintype "passive"))
      (node (ref "D1") (pin "2") (pinfunction "C_2") (pintype "passive"))
      (node (ref "D10") (pin "2") (pinfunction "C_2") (pintype "passive"))
      (node (ref "D11") (pin "2") (pinfunction "C_2") (pintype "passive"))
      (node (ref "D13") (pin "C") (pinfunction "C_C") (pintype "passive"))
      (node (ref "D2") (pin "2") (pinfunction "C_2") (pintype "passive"))
      (node (ref "D3") (pin "2") (pinfunction "C_2") (pintype "passive"))
      (node (ref "D4") (pin "2") (pinfunction "C_2") (pintype "passive"))
      (node (ref "D5") (pin "2") (pinfunction "C_2") (pintype "passive"))
      (node (ref "D6") (pin "2") (pinfunction "C_2") (pintype "passive"))
      (node (ref "D7") (pin "2") (pinfunction "C_2") (pintype "passive"))
      (node (ref "D8") (pin "2") (pinfunction "C_2") (pintype "passive"))
      (node (ref "D9") (pin "2") (pinfunction "C_2") (pintype "passive"))
      (node (ref "IC1") (pin "4") (pinfunction "EN/~{EN}_4") (pintype "bidirectional"))
      (node (ref "IC1") (pin "5") (pinfunction "IN_5") (pintype "bidirectional"))
      (node (ref "ICSP") (pin "2") (pinfunction "2_2") (pintype "bidirectional"))
      (node (ref "J2") (pin "2") (pinfunction "5V_2") (pintype "power_in"))
      (node (ref "J2") (pin "4") (pinfunction "5V_4") (pintype "power_in"))
      (node (ref "LED1") (pin "A") (pinfunction "A_A") (pintype "passive"))
      (node (ref "MCP1") (pin "15") (pinfunction "A0_15") (pintype "input"))
      (node (ref "MCP1") (pin "18") (pinfunction "~{RESET}_18") (pintype "input"))
      (node (ref "MCP1") (pin "9") (pinfunction "VDD_9") (pintype "power_in"))
      (node (ref "MCP2") (pin "18") (pinfunction "~{RESET}_18") (pintype "input"))
      (node (ref "MCP2") (pin "9") (pinfunction "VDD_9") (pintype "power_in"))
      (node (ref "R29") (pin "1") (pinfunction "1_1") (pintype "passive"))
      (node (ref "R50") (pin "2") (pinfunction "2_2") (pintype "passive"))
      (node (ref "R51") (pin "2") (pinfunction "2_2") (pintype "passive"))
      (node (ref "R52") (pin "2") (pinfunction "2_2") (pintype "passive"))
      (node (ref "R53") (pin "2") (pinfunction "2_2") (pintype "passive"))
      (node (ref "R54") (pin "2") (pinfunction "2_2") (pintype "passive"))
      (node (ref "R55") (pin "2") (pinfunction "2_2") (pintype "passive"))
      (node (ref "R56") (pin "2") (pinfunction "2_2") (pintype "passive"))
      (node (ref "R57") (pin "2") (pinfunction "2_2") (pintype "passive"))
      (node (ref "R58") (pin "2") (pinfunction "2_2") (pintype "passive"))
      (node (ref "R59") (pin "2") (pinfunction "2_2") (pintype "passive"))
      (node (ref "R60") (pin "2") (pinfunction "2_2") (pintype "passive"))
      (node (ref "R63") (pin "2") (pinfunction "2_2") (pintype "passive"))
      (node (ref "R67") (pin "2") (pinfunction "2_2") (pintype "passive"))
      (node (ref "R68") (pin "2") (pinfunction "2_2") (pintype "passive"))
      (node (ref "R69") (pin "2") (pinfunction "2_2") (pintype "passive"))
      (node (ref "R70") (pin "2") (pinfunction "2_2") (pintype "passive"))
      (node (ref "R71") (pin "2") (pinfunction "2_2") (pintype "passive"))
      (node (ref "R72") (pin "1") (pinfunction "1_1") (pintype "passive"))
      (node (ref "RPI-CM4") (pin "77") (pinfunction "+5V(INPUT)_77") (pintype "passive"))
      (node (ref "RPI-CM4") (pin "79") (pinfunction "+5V(INPUT)_79") (pintype "passive"))
      (node (ref "RPI-CM4") (pin "81") (pinfunction "+5V(INPUT)_81") (pintype "passive"))
      (node (ref "RPI-CM4") (pin "83") (pinfunction "+5V(INPUT)_83") (pintype "passive"))
      (node (ref "RPI-CM4") (pin "85") (pinfunction "+5V(INPUT)_85") (pintype "passive"))
      (node (ref "RPI-CM4") (pin "87") (pinfunction "+5V(INPUT)_87") (pintype "passive"))
      (node (ref "T1") (pin "3") (pinfunction "C_3") (pintype "passive"))
      (node (ref "T10") (pin "3") (pinfunction "C_3") (pintype "passive"))
      (node (ref "T11") (pin "3") (pinfunction "C_3") (pintype "passive"))
      (node (ref "T2") (pin "3") (pinfunction "C_3") (pintype "passive"))
      (node (ref "T3") (pin "3") (pinfunction "C_3") (pintype "passive"))
      (node (ref "T4") (pin "3") (pinfunction "C_3") (pintype "passive"))
      (node (ref "T5") (pin "3") (pinfunction "C_3") (pintype "passive"))
      (node (ref "T6") (pin "3") (pinfunction "C_3") (pintype "passive"))
      (node (ref "T7") (pin "3") (pinfunction "C_3") (pintype "passive"))
      (node (ref "T8") (pin "3") (pinfunction "C_3") (pintype "passive"))
      (node (ref "T9") (pin "3") (pinfunction "C_3") (pintype "passive"))
      (node (ref "U$5") (pin "P$3") (pinfunction "VOUT_P$3") (pintype "power_in"))
      (node (ref "U1") (pin "18") (pinfunction "AVCC_18") (pintype "power_in"))
      (node (ref "U1") (pin "4") (pinfunction "VCC_2_4") (pintype "power_in"))
      (node (ref "U1") (pin "6") (pinfunction "VCC_6") (pintype "power_in"))
      (node (ref "USB0") (pin "VBUS") (pinfunction "VBUS_VBUS") (pintype "power_in"))
    )
    (net (code "3") (name "+12V") (class "Default")
      (node (ref "C17") (pin "1") (pinfunction "1_1") (pintype "passive"))
      (node (ref "D12") (pin "C") (pinfunction "C_C") (pintype "passive"))
      (node (ref "POWER") (pin "2") (pinfunction "K_2") (pintype "passive"))
      (node (ref "R29") (pin "2") (pinfunction "2_2") (pintype "passive"))
      (node (ref "R72") (pin "2") (pinfunction "2_2") (pintype "passive"))
      (node (ref "U$5") (pin "P$1") (pinfunction "VIN_P$1") (pintype "power_in"))
    )
    (net (code "4") (name "5VHDMI") (class "Default")
      (node (ref "C18") (pin "1") (pinfunction "1_1") (pintype "passive"))
      (node (ref "HDMI0") (pin "P$18") (pinfunction "VCC_P$18") (pintype "bidirectional"))
      (node (ref "IC1") (pin "1") (pinfunction "OUT_1") (pintype "bidirectional"))
    )
    (net (code "5") (name "A") (class "Default")
      (node (ref "7SEG") (pin "7") (pinfunction "A_7") (pintype "passive"))
      (node (ref "R23") (pin "2") (pinfunction "2_2") (pintype "passive"))
    )
    (net (code "6") (name "A0") (class "Default")
      (node (ref "C15") (pin "1") (pinfunction "1_1") (pintype "passive"))
      (node (ref "R62") (pin "2") (pinfunction "2_2") (pintype "passive"))
      (node (ref "R63") (pin "1") (pinfunction "1_1") (pintype "passive"))
      (node (ref "U1") (pin "23") (pinfunction "PC0_23") (pintype "bidirectional"))
    )
    (net (code "7") (name "A1") (class "Default")
      (node (ref "C3") (pin "1") (pinfunction "1_1") (pintype "passive"))
      (node (ref "R42") (pin "2") (pinfunction "2_2") (pintype "passive"))
      (node (ref "R52") (pin "1") (pinfunction "1_1") (pintype "passive"))
      (node (ref "U1") (pin "24") (pinfunction "PC1_24") (pintype "bidirectional"))
    )
    (net (code "8") (name "A2") (class "Default")
      (node (ref "U1") (pin "25") (pinfunction "PC2_25") (pintype "bidirectional"))
    )
    (net (code "9") (name "A3") (class "Default")
      (node (ref "C10") (pin "1") (pinfunction "1_1") (pintype "passive"))
      (node (ref "R49") (pin "2") (pinfunction "2_2") (pintype "passive"))
      (node (ref "R59") (pin "1") (pinfunction "1_1") (pintype "passive"))
      (node (ref "U1") (pin "26") (pinfunction "PC3_26") (pintype "bidirectional"))
    )
    (net (code "10") (name "B") (class "Default")
      (node (ref "7SEG") (pin "6") (pinfunction "B_6") (pintype "passive"))
      (node (ref "R24") (pin "2") (pinfunction "2_2") (pintype "passive"))
    )
    (net (code "11") (name "BUZZ0") (class "Default")
      (node (ref "BUZZER0") (pin "2") (pinfunction "K_2") (pintype "passive"))
      (node (ref "R34") (pin "1") (pinfunction "1_1") (pintype "passive"))
      (node (ref "X2") (pin "26") (pinfunction "26_26") (pintype "passive"))
    )
    (net (code "12") (name "BUZZ1") (class "Default")
      (node (ref "BUZZER1") (pin "2") (pinfunction "K_2") (pintype "passive"))
      (node (ref "R39") (pin "1") (pinfunction "1_1") (pintype "passive"))
      (node (ref "X2") (pin "2") (pinfunction "2_2") (pintype "passive"))
    )
    (net (code "13") (name "BUZZ2") (class "Default")
      (node (ref "BUZZER2") (pin "2") (pinfunction "K_2") (pintype "passive"))
      (node (ref "R38") (pin "1") (pinfunction "1_1") (pintype "passive"))
      (node (ref "X2") (pin "4") (pinfunction "4_4") (pintype "passive"))
    )
    (net (code "14") (name "BUZZ3") (class "Default")
      (node (ref "BUZZER3") (pin "2") (pinfunction "K_2") (pintype "passive"))
      (node (ref "R37") (pin "1") (pinfunction "1_1") (pintype "passive"))
      (node (ref "X2") (pin "6") (pinfunction "6_6") (pintype "passive"))
    )
    (net (code "15") (name "BUZZ4") (class "Default")
      (node (ref "BUZZER4") (pin "2") (pinfunction "K_2") (pintype "passive"))
      (node (ref "R36") (pin "1") (pinfunction "1_1") (pintype "passive"))
      (node (ref "X2") (pin "10") (pinfunction "10_10") (pintype "passive"))
    )
    (net (code "16") (name "BUZZ5") (class "Default")
      (node (ref "BUZZER5") (pin "2") (pinfunction "K_2") (pintype "passive"))
      (node (ref "R35") (pin "1") (pinfunction "1_1") (pintype "passive"))
      (node (ref "X2") (pin "12") (pinfunction "12_12") (pintype "passive"))
    )
    (net (code "17") (name "BUZZ6") (class "Default")
      (node (ref "BUZZER6") (pin "2") (pinfunction "K_2") (pintype "passive"))
      (node (ref "R30") (pin "1") (pinfunction "1_1") (pintype "passive"))
      (node (ref "X2") (pin "14") (pinfunction "14_14") (pintype "passive"))
    )
    (net (code "18") (name "BUZZ7") (class "Default")
      (node (ref "BUZZER7") (pin "2") (pinfunction "K_2") (pintype "passive"))
      (node (ref "R31") (pin "1") (pinfunction "1_1") (pintype "passive"))
      (node (ref "X2") (pin "18") (pinfunction "18_18") (pintype "passive"))
    )
    (net (code "19") (name "BUZZ8") (class "Default")
      (node (ref "BUZZER8") (pin "2") (pinfunction "K_2") (pintype "passive"))
      (node (ref "R32") (pin "1") (pinfunction "1_1") (pintype "passive"))
      (node (ref "X2") (pin "20") (pinfunction "20_20") (pintype "passive"))
    )
    (net (code "20") (name "BUZZ9") (class "Default")
      (node (ref "BUZZER9") (pin "2") (pinfunction "K_2") (pintype "passive"))
      (node (ref "R33") (pin "1") (pinfunction "1_1") (pintype "passive"))
      (node (ref "X2") (pin "22") (pinfunction "22_22") (pintype "passive"))
    )
    (net (code "21") (name "C") (class "Default")
      (node (ref "7SEG") (pin "4") (pinfunction "C_4") (pintype "passive"))
      (node (ref "R26") (pin "2") (pinfunction "2_2") (pintype "passive"))
    )
    (net (code "22") (name "D") (class "Default")
      (node (ref "7SEG") (pin "2") (pinfunction "D_2") (pintype "passive"))
      (node (ref "R27") (pin "2") (pinfunction "2_2") (pintype "passive"))
    )
    (net (code "23") (name "D2") (class "Default")
      (node (ref "Q1") (pin "3") (pinfunction "D_3") (pintype "passive"))
      (node (ref "R67") (pin "1") (pinfunction "1_1") (pintype "passive"))
      (node (ref "U1") (pin "32") (pinfunction "PD2_32") (pintype "bidirectional"))
    )
    (net (code "24") (name "D3") (class "Default")
      (node (ref "C9") (pin "1") (pinfunction "1_1") (pintype "passive"))
      (node (ref "R48") (pin "2") (pinfunction "2_2") (pintype "passive"))
      (node (ref "R58") (pin "1") (pinfunction "1_1") (pintype "passive"))
      (node (ref "U1") (pin "1") (pinfunction "PD3_1") (pintype "bidirectional"))
    )
    (net (code "25") (name "D4") (class "Default")
      (node (ref "C8") (pin "1") (pinfunction "1_1") (pintype "passive"))
      (node (ref "R47") (pin "2") (pinfunction "2_2") (pintype "passive"))
      (node (ref "R57") (pin "1") (pinfunction "1_1") (pintype "passive"))
      (node (ref "U1") (pin "2") (pinfunction "PD4_2") (pintype "bidirectional"))
    )
    (net (code "26") (name "D5") (class "Default")
      (node (ref "C7") (pin "1") (pinfunction "1_1") (pintype "passive"))
      (node (ref "R46") (pin "2") (pinfunction "2_2") (pintype "passive"))
      (node (ref "R56") (pin "1") (pinfunction "1_1") (pintype "passive"))
      (node (ref "U1") (pin "9") (pinfunction "PD5_9") (pintype "bidirectional"))
    )
    (net (code "27") (name "D6") (class "Default")
      (node (ref "C6") (pin "1") (pinfunction "1_1") (pintype "passive"))
      (node (ref "R45") (pin "2") (pinfunction "2_2") (pintype "passive"))
      (node (ref "R55") (pin "1") (pinfunction "1_1") (pintype "passive"))
      (node (ref "U1") (pin "10") (pinfunction "PD6_10") (pintype "bidirectional"))
    )
    (net (code "28") (name "D7") (class "Default")
      (node (ref "C1") (pin "1") (pinfunction "1_1") (pintype "passive"))
      (node (ref "R40") (pin "2") (pinfunction "2_2") (pintype "passive"))
      (node (ref "R50") (pin "1") (pinfunction "1_1") (pintype "passive"))
      (node (ref "U1") (pin "11") (pinfunction "PD7_11") (pintype "bidirectional"))
    )
    (net (code "29") (name "D8") (class "Default")
      (node (ref "C2") (pin "1") (pinfunction "1_1") (pintype "passive"))
      (node (ref "R41") (pin "2") (pinfunction "2_2") (pintype "passive"))
      (node (ref "R51") (pin "1") (pinfunction "1_1") (pintype "passive"))
      (node (ref "U1") (pin "12") (pinfunction "PB0_12") (pintype "bidirectional"))
    )
    (net (code "30") (name "D9") (class "Default")
      (node (ref "C4") (pin "1") (pinfunction "1_1") (pintype "passive"))
      (node (ref "R43") (pin "2") (pinfunction "2_2") (pintype "passive"))
      (node (ref "R53") (pin "1") (pinfunction "1_1") (pintype "passive"))
      (node (ref "U1") (pin "13") (pinfunction "PB1_13") (pintype "bidirectional"))
    )
    (net (code "31") (name "D10") (class "Default")
      (node (ref "C5") (pin "1") (pinfunction "1_1") (pintype "passive"))
      (node (ref "R44") (pin "2") (pinfunction "2_2") (pintype "passive"))
      (node (ref "R54") (pin "1") (pinfunction "1_1") (pintype "passive"))
      (node (ref "U1") (pin "14") (pinfunction "PB2_14") (pintype "bidirectional"))
    )
    (net (code "32") (name "DP") (class "Default")
      (node (ref "7SEG") (pin "5") (pinfunction "DP_5") (pintype "passive"))
      (node (ref "R25") (pin "2") (pinfunction "2_2") (pintype "passive"))
    )
    (net (code "33") (name "E") (class "Default")
      (node (ref "7SEG") (pin "1") (pinfunction "E_1") (pintype "passive"))
      (node (ref "R28") (pin "2") (pinfunction "2_2") (pintype "passive"))
    )
    (net (code "34") (name "F") (class "Default")
      (node (ref "7SEG") (pin "9") (pinfunction "F_9") (pintype "passive"))
      (node (ref "R22") (pin "2") (pinfunction "2_2") (pintype "passive"))
    )
    (net (code "35") (name "G") (class "Default")
      (node (ref "7SEG") (pin "10") (pinfunction "G_10") (pintype "passive"))
      (node (ref "R21") (pin "2") (pinfunction "2_2") (pintype "passive"))
    )
    (net (code "36") (name "GND") (class "Default")
      (node (ref "BUZZER0") (pin "1") (pinfunction "K_1") (pintype "passive"))
      (node (ref "BUZZER1") (pin "1") (pinfunction "K_1") (pintype "passive"))
      (node (ref "BUZZER2") (pin "1") (pinfunction "K_1") (pintype "passive"))
      (node (ref "BUZZER3") (pin "1") (pinfunction "K_1") (pintype "passive"))
      (node (ref "BUZZER4") (pin "1") (pinfunction "K_1") (pintype "passive"))
      (node (ref "BUZZER5") (pin "1") (pinfunction "K_1") (pintype "passive"))
      (node (ref "BUZZER6") (pin "1") (pinfunction "K_1") (pintype "passive"))
      (node (ref "BUZZER7") (pin "1") (pinfunction "K_1") (pintype "passive"))
      (node (ref "BUZZER8") (pin "1") (pinfunction "K_1") (pintype "passive"))
      (node (ref "BUZZER9") (pin "1") (pinfunction "K_1") (pintype "passive"))
      (node (ref "C1") (pin "2") (pinfunction "2_2") (pintype "passive"))
      (node (ref "C10") (pin "2") (pinfunction "2_2") (pintype "passive"))
      (node (ref "C11") (pin "2") (pinfunction "-_2") (pintype "passive"))
      (node (ref "C12") (pin "2") (pinfunction "2_2") (pintype "passive"))
      (node (ref "C13") (pin "2") (pinfunction "2_2") (pintype "passive"))
      (node (ref "C14") (pin "2") (pinfunction "2_2") (pintype "passive"))
      (node (ref "C15") (pin "2") (pinfunction "2_2") (pintype "passive"))
      (node (ref "C16") (pin "1") (pinfunction "1_1") (pintype "passive"))
      (node (ref "C17") (pin "2") (pinfunction "2_2") (pintype "passive"))
      (node (ref "C18") (pin "2") (pinfunction "2_2") (pintype "passive"))
      (node (ref "C19") (pin "2") (pinfunction "2_2") (pintype "passive"))
      (node (ref "C2") (pin "2") (pinfunction "2_2") (pintype "passive"))
      (node (ref "C3") (pin "2") (pinfunction "2_2") (pintype "passive"))
      (node (ref "C4") (pin "2") (pinfunction "2_2") (pintype "passive"))
      (node (ref "C5") (pin "2") (pinfunction "2_2") (pintype "passive"))
      (node (ref "C6") (pin "2") (pinfunction "2_2") (pintype "passive"))
      (node (ref "C7") (pin "2") (pinfunction "2_2") (pintype "passive"))
      (node (ref "C8") (pin "2") (pinfunction "2_2") (pintype "passive"))
      (node (ref "C9") (pin "2") (pinfunction "2_2") (pintype "passive"))
      (node (ref "D1") (pin "1") (pinfunction "A_1") (pintype "passive"))
      (node (ref "D10") (pin "1") (pinfunction "A_1") (pintype "passive"))
      (node (ref "D11") (pin "1") (pinfunction "A_1") (pintype "passive"))
      (node (ref "D12") (pin "A") (pinfunction "A_A") (pintype "passive"))
      (node (ref "D13") (pin "A") (pinfunction "A_A") (pintype "passive"))
      (node (ref "D14") (pin "3") (pinfunction "GND_3") (pintype "power_in"))
      (node (ref "D2") (pin "1") (pinfunction "A_1") (pintype "passive"))
      (node (ref "D3") (pin "1") (pinfunction "A_1") (pintype "passive"))
      (node (ref "D4") (pin "1") (pinfunction "A_1") (pintype "passive"))
      (node (ref "D5") (pin "1") (pinfunction "A_1") (pintype "passive"))
      (node (ref "D6") (pin "1") (pinfunction "A_1") (pintype "passive"))
      (node (ref "D7") (pin "1") (pinfunction "A_1") (pintype "passive"))
      (node (ref "D8") (pin "1") (pinfunction "A_1") (pintype "passive"))
      (node (ref "D9") (pin "1") (pinfunction "A_1") (pintype "passive"))
      (node (ref "HDMI0") (pin "P$11") (pinfunction "CLOCKSHIELD_P$11") (pintype "bidirectional"))
      (node (ref "HDMI0") (pin "P$17") (pinfunction "CECGND_P$17") (pintype "bidirectional"))
      (node (ref "HDMI0") (pin "P$2") (pinfunction "DATA2SHIELD_P$2") (pintype "bidirectional"))
      (node (ref "HDMI0") (pin "P$24") (pinfunction "SHIELD_P$24") (pintype "bidirectional"))
      (node (ref "HDMI0") (pin "P$25") (pinfunction "SHIELD_P$25") (pintype "bidirectional"))
      (node (ref "HDMI0") (pin "P$26") (pinfunction "SHIELD_P$26") (pintype "bidirectional"))
      (node (ref "HDMI0") (pin "P$27") (pinfunction "SHIELD_P$27") (pintype "bidirectional"))
      (node (ref "HDMI0") (pin "P$5") (pinfunction "DATA1SHIELD_P$5") (pintype "bidirectional"))
      (node (ref "HDMI0") (pin "P$8") (pinfunction "DATA0SHIELD_P$8") (pintype "bidirectional"))
      (node (ref "IC1") (pin "2") (pinfunction "GND_2") (pintype "bidirectional"))
      (node (ref "ICSP") (pin "6") (pinfunction "6_6") (pintype "bidirectional"))
      (node (ref "J2") (pin "14") (pinfunction "GND_14") (pintype "power_in"))
      (node (ref "J2") (pin "20") (pinfunction "GND_20") (pintype "power_in"))
      (node (ref "J2") (pin "25") (pinfunction "GND_25") (pintype "power_in"))
      (node (ref "J2") (pin "30") (pinfunction "GND_30") (pintype "power_in"))
      (node (ref "J2") (pin "34") (pinfunction "GND_34") (pintype "power_in"))
      (node (ref "J2") (pin "39") (pinfunction "GND_39") (pintype "power_in"))
      (node (ref "J2") (pin "6") (pinfunction "GND_6") (pintype "power_in"))
      (node (ref "J2") (pin "9") (pinfunction "GND_9") (pintype "power_in"))
      (node (ref "MCP1") (pin "10") (pinfunction "VSS_10") (pintype "power_in"))
      (node (ref "MCP1") (pin "16") (pinfunction "A1_16") (pintype "input"))
      (node (ref "MCP1") (pin "17") (pinfunction "A2_17") (pintype "input"))
      (node (ref "MCP2") (pin "10") (pinfunction "VSS_10") (pintype "power_in"))
      (node (ref "MCP2") (pin "15") (pinfunction "A0_15") (pintype "input"))
      (node (ref "MCP2") (pin "16") (pinfunction "A1_16") (pintype "input"))
      (node (ref "MCP2") (pin "17") (pinfunction "A2_17") (pintype "input"))
      (node (ref "POWER") (pin "1") (pinfunction "K_1") (pintype "passive"))
      (node (ref "R74") (pin "2") (pinfunction "2_2") (pintype "passive"))
      (node (ref "RLSBT") (pin "1") (pinfunction "1_1") (pintype "passive"))
      (node (ref "RLSBT") (pin "4") (pinfunction "4_4") (pintype "passive"))
      (node (ref "RPI-CM4") (pin "1") (pinfunction "GND_1") (pintype "passive"))
      (node (ref "RPI-CM4") (pin "101") (pinfunction "USB_OTG_ID_101") (pintype "passive"))
      (node (ref "RPI-CM4") (pin "107") (pinfunction "GND_107") (pintype "passive"))
      (node (ref "RPI-CM4") (pin "108") (pinfunction "GND_108") (pintype "passive"))
      (node (ref "RPI-CM4") (pin "113") (pinfunction "GND_113") (pintype "passive"))
      (node (ref "RPI-CM4") (pin "114") (pinfunction "GND_114") (pintype "passive"))
      (node (ref "RPI-CM4") (pin "119") (pinfunction "GND_119") (pintype "passive"))
      (node (ref "RPI-CM4") (pin "120") (pinfunction "GND_120") (pintype "passive"))
      (node (ref "RPI-CM4") (pin "125") (pinfunction "GND_125") (pintype "passive"))
      (node (ref "RPI-CM4") (pin "126") (pinfunction "GND_126") (pintype "passive"))
      (node (ref "RPI-CM4") (pin "13") (pinfunction "GND_13") (pintype "passive"))
      (node (ref "RPI-CM4") (pin "131") (pinfunction "GND_131") (pintype "passive"))
      (node (ref "RPI-CM4") (pin "132") (pinfunction "GND_132") (pintype "passive"))
      (node (ref "RPI-CM4") (pin "137") (pinfunction "GND_137") (pintype "passive"))
      (node (ref "RPI-CM4") (pin "138") (pinfunction "GND_138") (pintype "passive"))
      (node (ref "RPI-CM4") (pin "14") (pinfunction "GND_14") (pintype "passive"))
      (node (ref "RPI-CM4") (pin "144") (pinfunction "GND_144") (pintype "passive"))
      (node (ref "RPI-CM4") (pin "150") (pinfunction "GND_150") (pintype "passive"))
      (node (ref "RPI-CM4") (pin "155") (pinfunction "GND_155") (pintype "passive"))
      (node (ref "RPI-CM4") (pin "156") (pinfunction "GND_156") (pintype "passive"))
      (node (ref "RPI-CM4") (pin "161") (pinfunction "GND_161") (pintype "passive"))
      (node (ref "RPI-CM4") (pin "162") (pinfunction "GND_162") (pintype "passive"))
      (node (ref "RPI-CM4") (pin "167") (pinfunction "GND_167") (pintype "passive"))
      (node (ref "RPI-CM4") (pin "168") (pinfunction "GND_168") (pintype "passive"))
      (node (ref "RPI-CM4") (pin "173") (pinfunction "GND_173") (pintype "passive"))
      (node (ref "RPI-CM4") (pin "174") (pinfunction "GND_174") (pintype "passive"))
      (node (ref "RPI-CM4") (pin "179") (pinfunction "GND_179") (pintype "passive"))
      (node (ref "RPI-CM4") (pin "180") (pinfunction "GND_180") (pintype "passive"))
      (node (ref "RPI-CM4") (pin "185") (pinfunction "GND_185") (pintype "passive"))
      (node (ref "RPI-CM4") (pin "186") (pinfunction "GND_186") (pintype "passive"))
      (node (ref "RPI-CM4") (pin "191") (pinfunction "GND_191") (pintype "passive"))
      (node (ref "RPI-CM4") (pin "192") (pinfunction "GND_192") (pintype "passive"))
      (node (ref "RPI-CM4") (pin "197") (pinfunction "GND_197") (pintype "passive"))
      (node (ref "RPI-CM4") (pin "198") (pinfunction "GND_198") (pintype "passive"))
      (node (ref "RPI-CM4") (pin "2") (pinfunction "GND_2") (pintype "passive"))
      (node (ref "RPI-CM4") (pin "20") (pinfunction "EEPROM_~{WP}_20") (pintype "passive"))
      (node (ref "RPI-CM4") (pin "22") (pinfunction "GND_22") (pintype "passive"))
      (node (ref "RPI-CM4") (pin "23") (pinfunction "GND_23") (pintype "passive"))
      (node (ref "RPI-CM4") (pin "32") (pinfunction "GND_32") (pintype "passive"))
      (node (ref "RPI-CM4") (pin "33") (pinfunction "GND_33") (pintype "passive"))
      (node (ref "RPI-CM4") (pin "42") (pinfunction "GND_42") (pintype "passive"))
      (node (ref "RPI-CM4") (pin "43") (pinfunction "GND_43") (pintype "passive"))
      (node (ref "RPI-CM4") (pin "52") (pinfunction "GND_52") (pintype "passive"))
      (node (ref "RPI-CM4") (pin "53") (pinfunction "GND_53") (pintype "passive"))
      (node (ref "RPI-CM4") (pin "59") (pinfunction "GND_59") (pintype "passive"))
      (node (ref "RPI-CM4") (pin "60") (pinfunction "GND_60") (pintype "passive"))
      (node (ref "RPI-CM4") (pin "65") (pinfunction "GND_65") (pintype "passive"))
      (node (ref "RPI-CM4") (pin "66") (pinfunction "GND_66") (pintype "passive"))
      (node (ref "RPI-CM4") (pin "7") (pinfunction "GND_7") (pintype "passive"))
      (node (ref "RPI-CM4") (pin "71") (pinfunction "GND_71") (pintype "passive"))
      (node (ref "RPI-CM4") (pin "74") (pinfunction "GND_74") (pintype "passive"))
      (node (ref "RPI-CM4") (pin "8") (pinfunction "GND_8") (pintype "passive"))
      (node (ref "RPI-CM4") (pin "98") (pinfunction "GND_98") (pintype "passive"))
      (node (ref "U$5") (pin "P$2") (pinfunction "GND_P$2") (pintype "power_in"))
      (node (ref "U1") (pin "21") (pinfunction "GND_21") (pintype "passive"))
      (node (ref "U1") (pin "3") (pinfunction "GND_2_3") (pintype "passive"))
      (node (ref "U1") (pin "5") (pinfunction "GND_3_5") (pintype "passive"))
      (node (ref "USB0") (pin "GND") (pinfunction "GND_GND") (pintype "power_in"))
      (node (ref "USB0") (pin "SHLD1") (pinfunction "SHIELD_SHLD1") (pintype "bidirectional"))
      (node (ref "USB0") (pin "SHLD2") (pinfunction "SHIELD_SHLD2") (pintype "bidirectional"))
      (node (ref "X2") (pin "15") (pinfunction "15_15") (pintype "passive"))
      (node (ref "X2") (pin "16") (pinfunction "16_16") (pintype "passive"))
      (node (ref "X2") (pin "23") (pinfunction "23_23") (pintype "passive"))
      (node (ref "X2") (pin "24") (pinfunction "24_24") (pintype "passive"))
      (node (ref "X2") (pin "7") (pinfunction "7_7") (pintype "passive"))
      (node (ref "X2") (pin "8") (pinfunction "8_8") (pintype "passive"))
      (node (ref "Y1") (pin "2") (pinfunction "2_2") (pintype "passive"))
    )
    (net (code "37") (name "GP2") (class "Default")
      (node (ref "RPI-CM4") (pin "58") (pinfunction "GPIO2_58") (pintype "passive"))
    )
    (net (code "38") (name "GP3") (class "Default")
      (node (ref "RPI-CM4") (pin "56") (pinfunction "GPIO3_56") (pintype "passive"))
    )
    (net (code "39") (name "GP4") (class "Default")
      (node (ref "J2") (pin "7") (pinfunction "GP4_7") (pintype "bidirectional"))
      (node (ref "RPI-CM4") (pin "54") (pinfunction "GPIO4_54") (pintype "passive"))
    )
    (net (code "40") (name "GP5") (class "Default")
      (node (ref "J2") (pin "29") (pinfunction "GP5_29") (pintype "bidirectional"))
      (node (ref "RPI-CM4") (pin "34") (pinfunction "GPIO5_34") (pintype "passive"))
    )
    (net (code "41") (name "GP6") (class "Default")
      (node (ref "J2") (pin "31") (pinfunction "GP6_31") (pintype "bidirectional"))
      (node (ref "RPI-CM4") (pin "30") (pinfunction "GPIO6_30") (pintype "passive"))
    )
    (net (code "42") (name "GP7") (class "Default")
      (node (ref "J2") (pin "26") (pinfunction "CE1_26") (pintype "output"))
      (node (ref "RPI-CM4") (pin "37") (pinfunction "GPIO7_37") (pintype "passive"))
    )
    (net (code "43") (name "GP8") (class "Default")
      (node (ref "J2") (pin "24") (pinfunction "CE0_24") (pintype "output"))
      (node (ref "RPI-CM4") (pin "39") (pinfunction "GPIO8_39") (pintype "passive"))
    )
    (net (code "44") (name "GP9") (class "Default")
      (node (ref "J2") (pin "21") (pinfunction "MISO_21") (pintype "input"))
      (node (ref "RPI-CM4") (pin "40") (pinfunction "GPIO9_40") (pintype "passive"))
    )
    (net (code "45") (name "GP10") (class "Default")
      (node (ref "J2") (pin "19") (pinfunction "MOSI_19") (pintype "output"))
      (node (ref "RPI-CM4") (pin "44") (pinfunction "GPIO10_44") (pintype "passive"))
    )
    (net (code "46") (name "GP11") (class "Default")
      (node (ref "J2") (pin "23") (pinfunction "SCLK_23") (pintype "output"))
      (node (ref "RPI-CM4") (pin "38") (pinfunction "GPIO11_38") (pintype "passive"))
    )
    (net (code "47") (name "GP12") (class "Default")
      (node (ref "J2") (pin "32") (pinfunction "GP12_32") (pintype "bidirectional"))
      (node (ref "RPI-CM4") (pin "31") (pinfunction "GPIO12_31") (pintype "passive"))
    )
    (net (code "48") (name "GP13") (class "Default")
      (node (ref "J2") (pin "33") (pinfunction "GP13_33") (pintype "bidirectional"))
      (node (ref "RPI-CM4") (pin "28") (pinfunction "GPIO13_28") (pintype "passive"))
    )
    (net (code "49") (name "GP16") (class "Default")
      (node (ref "J2") (pin "36") (pinfunction "GP16_36") (pintype "bidirectional"))
      (node (ref "RPI-CM4") (pin "29") (pinfunction "GPIO16_29") (pintype "passive"))
    )
    (net (code "50") (name "GP17") (class "Default")
      (node (ref "J2") (pin "11") (pinfunction "GP17_11") (pintype "bidirectional"))
      (node (ref "RPI-CM4") (pin "50") (pinfunction "GPIO17_50") (pintype "passive"))
    )
    (net (code "51") (name "GP18") (class "Default")
      (node (ref "J2") (pin "12") (pinfunction "GP18#_12") (pintype "bidirectional"))
      (node (ref "RPI-CM4") (pin "49") (pinfunction "GPIO18_49") (pintype "passive"))
    )
    (net (code "52") (name "GP19") (class "Default")
      (node (ref "J2") (pin "35") (pinfunction "GP19_35") (pintype "bidirectional"))
      (node (ref "RPI-CM4") (pin "26") (pinfunction "GPIO19_26") (pintype "passive"))
    )
    (net (code "53") (name "GP20") (class "Default")
      (node (ref "J2") (pin "38") (pinfunction "GP20_38") (pintype "bidirectional"))
      (node (ref "RPI-CM4") (pin "27") (pinfunction "GPIO20_27") (pintype "passive"))
    )
    (net (code "54") (name "GP21") (class "Default")
      (node (ref "J2") (pin "40") (pinfunction "GP21_40") (pintype "bidirectional"))
      (node (ref "RPI-CM4") (pin "25") (pinfunction "GPIO21_25") (pintype "passive"))
    )
    (net (code "55") (name "GP22") (class "Default")
      (node (ref "J2") (pin "15") (pinfunction "GP22_15") (pintype "bidirectional"))
      (node (ref "RPI-CM4") (pin "46") (pinfunction "GPIO22_46") (pintype "passive"))
    )
    (net (code "56") (name "GP23") (class "Default")
      (node (ref "J2") (pin "16") (pinfunction "GP23_16") (pintype "bidirectional"))
      (node (ref "Q1") (pin "2") (pinfunction "S_2") (pintype "passive"))
      (node (ref "R64") (pin "1") (pinfunction "1_1") (pintype "passive"))
      (node (ref "RPI-CM4") (pin "47") (pinfunction "GPIO23_47") (pintype "passive"))
    )
    (net (code "57") (name "GP24") (class "Default")
      (node (ref "J2") (pin "18") (pinfunction "GP24_18") (pintype "bidirectional"))
      (node (ref "RPI-CM4") (pin "45") (pinfunction "GPIO24_45") (pintype "passive"))
    )
    (net (code "58") (name "GP25") (class "Default")
      (node (ref "J2") (pin "22") (pinfunction "GP25_22") (pintype "bidirectional"))
      (node (ref "RPI-CM4") (pin "41") (pinfunction "GPIO25_41") (pintype "passive"))
    )
    (net (code "59") (name "GP26") (class "Default")
      (node (ref "J2") (pin "37") (pinfunction "GP26_37") (pintype "bidirectional"))
      (node (ref "RPI-CM4") (pin "24") (pinfunction "GPIO26_24") (pintype "passive"))
    )
    (net (code "60") (name "GP27") (class "Default")
      (node (ref "J2") (pin "13") (pinfunction "GP27_13") (pintype "bidirectional"))
      (node (ref "RPI-CM4") (pin "48") (pinfunction "GPIO27_48") (pintype "passive"))
    )
    (net (code "61") (name "GPA0") (class "Default")
      (node (ref "MCP2") (pin "21") (pinfunction "GPA0_21") (pintype "bidirectional"))
      (node (ref "R18") (pin "1") (pinfunction "1_1") (pintype "passive"))
    )
    (net (code "62") (name "GPA1") (class "Default")
      (node (ref "MCP2") (pin "22") (pinfunction "GPA1_22") (pintype "bidirectional"))
      (node (ref "R17") (pin "1") (pinfunction "1_1") (pintype "passive"))
    )
    (net (code "63") (name "GPA2") (class "Default")
      (node (ref "MCP2") (pin "23") (pinfunction "GPA2_23") (pintype "bidirectional"))
      (node (ref "R11") (pin "1") (pinfunction "1_1") (pintype "passive"))
    )
    (net (code "64") (name "GPA3") (class "Default")
      (node (ref "MCP2") (pin "24") (pinfunction "GPA3_24") (pintype "bidirectional"))
      (node (ref "R12") (pin "1") (pinfunction "1_1") (pintype "passive"))
    )
    (net (code "65") (name "GPA4") (class "Default")
      (node (ref "MCP2") (pin "25") (pinfunction "GPA4_25") (pintype "bidirectional"))
      (node (ref "R13") (pin "1") (pinfunction "1_1") (pintype "passive"))
    )
    (net (code "66") (name "GPA5") (class "Default")
      (node (ref "MCP2") (pin "26") (pinfunction "GPA5_26") (pintype "bidirectional"))
      (node (ref "R14") (pin "1") (pinfunction "1_1") (pintype "passive"))
    )
    (net (code "67") (name "GPA6") (class "Default")
      (node (ref "MCP2") (pin "27") (pinfunction "GPA6_27") (pintype "bidirectional"))
      (node (ref "R15") (pin "1") (pinfunction "1_1") (pintype "passive"))
    )
    (net (code "68") (name "GPA7") (class "Default")
      (node (ref "MCP2") (pin "28") (pinfunction "GPA7_28") (pintype "bidirectional"))
      (node (ref "R16") (pin "1") (pinfunction "1_1") (pintype "passive"))
    )
    (net (code "69") (name "GPB0") (class "Default")
      (node (ref "MCP2") (pin "1") (pinfunction "GPB0_1") (pintype "bidirectional"))
      (node (ref "R20") (pin "1") (pinfunction "1_1") (pintype "passive"))
    )
    (net (code "70") (name "GPB1") (class "Default")
      (node (ref "MCP2") (pin "2") (pinfunction "GPB1_2") (pintype "bidirectional"))
      (node (ref "R19") (pin "1") (pinfunction "1_1") (pintype "passive"))
    )
    (net (code "71") (name "HDMI_CEC") (class "Default")
      (node (ref "HDMI0") (pin "P$13") (pinfunction "CEC_P$13") (pintype "bidirectional"))
      (node (ref "RPI-CM4") (pin "151") (pinfunction "HDMI0_CEC_151") (pintype "passive"))
    )
    (net (code "72") (name "HDMI_CLK_N") (class "Default")
      (node (ref "HDMI0") (pin "P$12") (pinfunction "CLOCK-_P$12") (pintype "bidirectional"))
      (node (ref "RPI-CM4") (pin "190") (pinfunction "HDMI0_CLK_N_190") (pintype "passive"))
    )
    (net (code "73") (name "HDMI_CLK_P") (class "Default")
      (node (ref "HDMI0") (pin "P$10") (pinfunction "CLOCK+_P$10") (pintype "bidirectional"))
      (node (ref "RPI-CM4") (pin "188") (pinfunction "HDMI0_CLK_P_188") (pintype "passive"))
    )
    (net (code "74") (name "HDMI_D0_N") (class "Default")
      (node (ref "HDMI0") (pin "P$9") (pinfunction "DATA0-_P$9") (pintype "bidirectional"))
      (node (ref "RPI-CM4") (pin "184") (pinfunction "HDMI0_TX0_N_184") (pintype "passive"))
    )
    (net (code "75") (name "HDMI_D0_P") (class "Default")
      (node (ref "HDMI0") (pin "P$7") (pinfunction "DATA0+_P$7") (pintype "bidirectional"))
      (node (ref "RPI-CM4") (pin "182") (pinfunction "HDMI0_TX0_P_182") (pintype "passive"))
    )
    (net (code "76") (name "HDMI_D1_N") (class "Default")
      (node (ref "HDMI0") (pin "P$6") (pinfunction "DATA1-_P$6") (pintype "bidirectional"))
      (node (ref "RPI-CM4") (pin "178") (pinfunction "HDMI0_TX1_N_178") (pintype "passive"))
    )
    (net (code "77") (name "HDMI_D1_P") (class "Default")
      (node (ref "HDMI0") (pin "P$4") (pinfunction "DATA1+_P$4") (pintype "bidirectional"))
      (node (ref "RPI-CM4") (pin "176") (pinfunction "HDMI0_TX1_P_176") (pintype "passive"))
    )
    (net (code "78") (name "HDMI_D2_N") (class "Default")
      (node (ref "HDMI0") (pin "P$3") (pinfunction "DATA2-_P$3") (pintype "bidirectional"))
      (node (ref "RPI-CM4") (pin "172") (pinfunction "HDMI0_TX2_N_172") (pintype "passive"))
    )
    (net (code "79") (name "HDMI_D2_P") (class "Default")
      (node (ref "HDMI0") (pin "P$1") (pinfunction "DATA2+_P$1") (pintype "bidirectional"))
      (node (ref "RPI-CM4") (pin "170") (pinfunction "HDMI0_TX2_P_170") (pintype "passive"))
    )
    (net (code "80") (name "HDMI_HOT") (class "Default")
      (node (ref "HDMI0") (pin "P$19") (pinfunction "HOTPLUG_P$19") (pintype "bidirectional"))
      (node (ref "RPI-CM4") (pin "153") (pinfunction "HDMI0_HOTPLUG_153") (pintype "passive"))
    )
    (net (code "81") (name "HDMI_SCL") (class "Default")
      (node (ref "HDMI0") (pin "P$15") (pinfunction "SCL_P$15") (pintype "bidirectional"))
      (node (ref "RPI-CM4") (pin "200") (pinfunction "HDMI0_SCL_200") (pintype "passive"))
    )
    (net (code "82") (name "HDMI_SDA") (class "Default")
      (node (ref "HDMI0") (pin "P$16") (pinfunction "SDA_P$16") (pintype "bidirectional"))
      (node (ref "RPI-CM4") (pin "199") (pinfunction "HDMI0_SDA_199") (pintype "passive"))
    )
    (net (code "83") (name "ID_SC") (class "Default")
      (node (ref "J2") (pin "28") (pinfunction "ID_SC_28") (pintype "bidirectional"))
      (node (ref "RPI-CM4") (pin "35") (pinfunction "ID_SC_35") (pintype "passive"))
    )
    (net (code "84") (name "ID_SD") (class "Default")
      (node (ref "J2") (pin "27") (pinfunction "ID_SD_27") (pintype "bidirectional"))
      (node (ref "RPI-CM4") (pin "36") (pinfunction "ID_SD_36") (pintype "passive"))
    )
    (net (code "85") (name "LED0A2") (class "Default")
      (node (ref "BUZZER6") (pin "3") (pinfunction "K_3") (pintype "passive"))
      (node (ref "R1") (pin "1") (pinfunction "1_1") (pintype "passive"))
      (node (ref "X2") (pin "13") (pinfunction "13_13") (pintype "passive"))
    )
    (net (code "86") (name "LED0A3") (class "Default")
      (node (ref "BUZZER5") (pin "3") (pinfunction "K_3") (pintype "passive"))
      (node (ref "R2") (pin "1") (pinfunction "1_1") (pintype "passive"))
      (node (ref "X2") (pin "11") (pinfunction "11_11") (pintype "passive"))
    )
    (net (code "87") (name "LED0A4") (class "Default")
      (node (ref "BUZZER4") (pin "3") (pinfunction "K_3") (pintype "passive"))
      (node (ref "R3") (pin "1") (pinfunction "1_1") (pintype "passive"))
      (node (ref "X2") (pin "9") (pinfunction "9_9") (pintype "passive"))
    )
    (net (code "88") (name "LED0B0") (class "Default")
      (node (ref "BUZZER7") (pin "3") (pinfunction "K_3") (pintype "passive"))
      (node (ref "R10") (pin "1") (pinfunction "1_1") (pintype "passive"))
      (node (ref "X2") (pin "17") (pinfunction "17_17") (pintype "passive"))
    )
    (net (code "89") (name "LED0B1") (class "Default")
      (node (ref "BUZZER8") (pin "3") (pinfunction "K_3") (pintype "passive"))
      (node (ref "R9") (pin "1") (pinfunction "1_1") (pintype "passive"))
      (node (ref "X2") (pin "19") (pinfunction "19_19") (pintype "passive"))
    )
    (net (code "90") (name "LED1A0") (class "Default")
      (node (ref "BUZZER9") (pin "3") (pinfunction "K_3") (pintype "passive"))
      (node (ref "R8") (pin "1") (pinfunction "1_1") (pintype "passive"))
      (node (ref "X2") (pin "21") (pinfunction "21_21") (pintype "passive"))
    )
    (net (code "91") (name "LED1A1") (class "Default")
      (node (ref "BUZZER0") (pin "3") (pinfunction "K_3") (pintype "passive"))
      (node (ref "R7") (pin "1") (pinfunction "1_1") (pintype "passive"))
      (node (ref "X2") (pin "25") (pinfunction "25_25") (pintype "passive"))
    )
    (net (code "92") (name "LED1A5") (class "Default")
      (node (ref "BUZZER3") (pin "3") (pinfunction "K_3") (pintype "passive"))
      (node (ref "R4") (pin "1") (pinfunction "1_1") (pintype "passive"))
      (node (ref "X2") (pin "5") (pinfunction "5_5") (pintype "passive"))
    )
    (net (code "93") (name "LED1A6") (class "Default")
      (node (ref "BUZZER2") (pin "3") (pinfunction "K_3") (pintype "passive"))
      (node (ref "R5") (pin "1") (pinfunction "1_1") (pintype "passive"))
      (node (ref "X2") (pin "3") (pinfunction "3_3") (pintype "passive"))
    )
    (net (code "94") (name "LED1A7") (class "Default")
      (node (ref "BUZZER1") (pin "3") (pinfunction "K_3") (pintype "passive"))
      (node (ref "R6") (pin "1") (pinfunction "1_1") (pintype "passive"))
      (node (ref "X2") (pin "1") (pinfunction "1_1") (pintype "passive"))
    )
    (net (code "95") (name "MISO") (class "Default")
      (node (ref "ICSP") (pin "1") (pinfunction "1_1") (pintype "bidirectional"))
      (node (ref "U1") (pin "16") (pinfunction "PB4_16") (pintype "bidirectional"))
    )
    (net (code "96") (name "MOSI") (class "Default")
      (node (ref "ICSP") (pin "4") (pinfunction "4_4") (pintype "bidirectional"))
      (node (ref "U1") (pin "15") (pinfunction "PB3_15") (pintype "bidirectional"))
    )
    (net (code "97") (name "Net-(D1-AC)") (class "Default")
      (node (ref "D1") (pin "3") (pinfunction "AC_3") (pintype "passive"))
      (node (ref "R30") (pin "2") (pinfunction "2_2") (pintype "passive"))
      (node (ref "R40") (pin "1") (pinfunction "1_1") (pintype "passive"))
    )
    (net (code "98") (name "Net-(D2-AC)") (class "Default")
      (node (ref "D2") (pin "3") (pinfunction "AC_3") (pintype "passive"))
      (node (ref "R31") (pin "2") (pinfunction "2_2") (pintype "passive"))
      (node (ref "R41") (pin "1") (pinfunction "1_1") (pintype "passive"))
    )
    (net (code "99") (name "Net-(D3-AC)") (class "Default")
      (node (ref "D3") (pin "3") (pinfunction "AC_3") (pintype "passive"))
      (node (ref "R32") (pin "2") (pinfunction "2_2") (pintype "passive"))
      (node (ref "R42") (pin "1") (pinfunction "1_1") (pintype "passive"))
    )
    (net (code "100") (name "Net-(D4-AC)") (class "Default")
      (node (ref "D4") (pin "3") (pinfunction "AC_3") (pintype "passive"))
      (node (ref "R33") (pin "2") (pinfunction "2_2") (pintype "passive"))
      (node (ref "R43") (pin "1") (pinfunction "1_1") (pintype "passive"))
    )
    (net (code "101") (name "Net-(D5-AC)") (class "Default")
      (node (ref "D5") (pin "3") (pinfunction "AC_3") (pintype "passive"))
      (node (ref "R34") (pin "2") (pinfunction "2_2") (pintype "passive"))
      (node (ref "R44") (pin "1") (pinfunction "1_1") (pintype "passive"))
    )
    (net (code "102") (name "Net-(D6-AC)") (class "Default")
      (node (ref "D6") (pin "3") (pinfunction "AC_3") (pintype "passive"))
      (node (ref "R35") (pin "2") (pinfunction "2_2") (pintype "passive"))
      (node (ref "R45") (pin "1") (pinfunction "1_1") (pintype "passive"))
    )
    (net (code "103") (name "Net-(D7-AC)") (class "Default")
      (node (ref "D7") (pin "3") (pinfunction "AC_3") (pintype "passive"))
      (node (ref "R36") (pin "2") (pinfunction "2_2") (pintype "passive"))
      (node (ref "R46") (pin "1") (pinfunction "1_1") (pintype "passive"))
    )
    (net (code "104") (name "Net-(D8-AC)") (class "Default")
      (node (ref "D8") (pin "3") (pinfunction "AC_3") (pintype "passive"))
      (node (ref "R37") (pin "2") (pinfunction "2_2") (pintype "passive"))
      (node (ref "R47") (pin "1") (pinfunction "1_1") (pintype "passive"))
    )
    (net (code "105") (name "Net-(D9-AC)") (class "Default")
      (node (ref "D9") (pin "3") (pinfunction "AC_3") (pintype "passive"))
      (node (ref "R38") (pin "2") (pinfunction "2_2") (pintype "passive"))
      (node (ref "R48") (pin "1") (pinfunction "1_1") (pintype "passive"))
    )
    (net (code "106") (name "Net-(D10-AC)") (class "Default")
      (node (ref "D10") (pin "3") (pinfunction "AC_3") (pintype "passive"))
      (node (ref "R39") (pin "2") (pinfunction "2_2") (pintype "passive"))
      (node (ref "R49") (pin "1") (pinfunction "1_1") (pintype "passive"))
    )
    (net (code "107") (name "Net-(D11-AC)") (class "Default")
      (node (ref "D11") (pin "3") (pinfunction "AC_3") (pintype "passive"))
      (node (ref "R61") (pin "2") (pinfunction "2_2") (pintype "passive"))
      (node (ref "R62") (pin "1") (pinfunction "1_1") (pintype "passive"))
    )
    (net (code "108") (name "Net-(LED1-PadC)") (class "Default")
      (node (ref "LED1") (pin "C") (pinfunction "C_C") (pintype "passive"))
      (node (ref "R74") (pin "1") (pinfunction "1_1") (pintype "passive"))
    )
    (net (code "109") (name "Net-(LED3-PadC)") (class "Default")
      (node (ref "LED3") (pin "C") (pinfunction "C_C") (pintype "passive"))
      (node (ref "R73") (pin "1") (pinfunction "1_1") (pintype "passive"))
    )
    (net (code "110") (name "Net-(R61-Pad1)") (class "Default")
      (node (ref "R61") (pin "1") (pinfunction "1_1") (pintype "passive"))
      (node (ref "RLSBT") (pin "2") (pinfunction "2_2") (pintype "passive"))
    )
    (net (code "111") (name "Net-(R75-Pad1)") (class "Default")
      (node (ref "R75") (pin "1") (pinfunction "1_1") (pintype "passive"))
      (node (ref "RLSBT") (pin "3") (pinfunction "3_3") (pintype "passive"))
    )
    (net (code "112") (name "Net-(RPI-CM4A-PI_~{LED_ACTIVITY})") (class "Default")
      (node (ref "R73") (pin "2") (pinfunction "2_2") (pintype "passive"))
      (node (ref "RPI-CM4") (pin "21") (pinfunction "PI_~{LED_ACTIVITY}_21") (pintype "passive"))
    )
    (net (code "113") (name "Net-(T1-B)") (class "Default")
      (node (ref "R11") (pin "2") (pinfunction "2_2") (pintype "passive"))
      (node (ref "T1") (pin "1") (pinfunction "B_1") (pintype "passive"))
    )
    (net (code "114") (name "Net-(T1-E)") (class "Default")
      (node (ref "R1") (pin "2") (pinfunction "2_2") (pintype "passive"))
      (node (ref "T1") (pin "2") (pinfunction "E_2") (pintype "passive"))
    )
    (net (code "115") (name "Net-(T2-B)") (class "Default")
      (node (ref "R12") (pin "2") (pinfunction "2_2") (pintype "passive"))
      (node (ref "T2") (pin "1") (pinfunction "B_1") (pintype "passive"))
    )
    (net (code "116") (name "Net-(T2-E)") (class "Default")
      (node (ref "R2") (pin "2") (pinfunction "2_2") (pintype "passive"))
      (node (ref "T2") (pin "2") (pinfunction "E_2") (pintype "passive"))
    )
    (net (code "117") (name "Net-(T3-B)") (class "Default")
      (node (ref "R13") (pin "2") (pinfunction "2_2") (pintype "passive"))
      (node (ref "T3") (pin "1") (pinfunction "B_1") (pintype "passive"))
    )
    (net (code "118") (name "Net-(T3-E)") (class "Default")
      (node (ref "R3") (pin "2") (pinfunction "2_2") (pintype "passive"))
      (node (ref "T3") (pin "2") (pinfunction "E_2") (pintype "passive"))
    )
    (net (code "119") (name "Net-(T4-B)") (class "Default")
      (node (ref "R14") (pin "2") (pinfunction "2_2") (pintype "passive"))
      (node (ref "T4") (pin "1") (pinfunction "B_1") (pintype "passive"))
    )
    (net (code "120") (name "Net-(T4-E)") (class "Default")
      (node (ref "R4") (pin "2") (pinfunction "2_2") (pintype "passive"))
      (node (ref "T4") (pin "2") (pinfunction "E_2") (pintype "passive"))
    )
    (net (code "121") (name "Net-(T5-B)") (class "Default")
      (node (ref "R15") (pin "2") (pinfunction "2_2") (pintype "passive"))
      (node (ref "T5") (pin "1") (pinfunction "B_1") (pintype "passive"))
    )
    (net (code "122") (name "Net-(T5-E)") (class "Default")
      (node (ref "R5") (pin "2") (pinfunction "2_2") (pintype "passive"))
      (node (ref "T5") (pin "2") (pinfunction "E_2") (pintype "passive"))
    )
    (net (code "123") (name "Net-(T6-B)") (class "Default")
      (node (ref "R16") (pin "2") (pinfunction "2_2") (pintype "passive"))
      (node (ref "T6") (pin "1") (pinfunction "B_1") (pintype "passive"))
    )
    (net (code "124") (name "Net-(T6-E)") (class "Default")
      (node (ref "R6") (pin "2") (pinfunction "2_2") (pintype "passive"))
      (node (ref "T6") (pin "2") (pinfunction "E_2") (pintype "passive"))
    )
    (net (code "125") (name "Net-(T7-B)") (class "Default")
      (node (ref "R17") (pin "2") (pinfunction "2_2") (pintype "passive"))
      (node (ref "T7") (pin "1") (pinfunction "B_1") (pintype "passive"))
    )
    (net (code "126") (name "Net-(T7-E)") (class "Default")
      (node (ref "R7") (pin "2") (pinfunction "2_2") (pintype "passive"))
      (node (ref "T7") (pin "2") (pinfunction "E_2") (pintype "passive"))
    )
    (net (code "127") (name "Net-(T8-B)") (class "Default")
      (node (ref "R18") (pin "2") (pinfunction "2_2") (pintype "passive"))
      (node (ref "T8") (pin "1") (pinfunction "B_1") (pintype "passive"))
    )
    (net (code "128") (name "Net-(T8-E)") (class "Default")
      (node (ref "R8") (pin "2") (pinfunction "2_2") (pintype "passive"))
      (node (ref "T8") (pin "2") (pinfunction "E_2") (pintype "passive"))
    )
    (net (code "129") (name "Net-(T9-B)") (class "Default")
      (node (ref "R19") (pin "2") (pinfunction "2_2") (pintype "passive"))
      (node (ref "T9") (pin "1") (pinfunction "B_1") (pintype "passive"))
    )
    (net (code "130") (name "Net-(T9-E)") (class "Default")
      (node (ref "R9") (pin "2") (pinfunction "2_2") (pintype "passive"))
      (node (ref "T9") (pin "2") (pinfunction "E_2") (pintype "passive"))
    )
    (net (code "131") (name "Net-(T10-B)") (class "Default")
      (node (ref "R20") (pin "2") (pinfunction "2_2") (pintype "passive"))
      (node (ref "T10") (pin "1") (pinfunction "B_1") (pintype "passive"))
    )
    (net (code "132") (name "Net-(T10-E)") (class "Default")
      (node (ref "R10") (pin "2") (pinfunction "2_2") (pintype "passive"))
      (node (ref "T10") (pin "2") (pinfunction "E_2") (pintype "passive"))
    )
    (net (code "133") (name "Net-(T11-B)") (class "Default")
      (node (ref "R75") (pin "2") (pinfunction "2_2") (pintype "passive"))
      (node (ref "T11") (pin "1") (pinfunction "B_1") (pintype "passive"))
    )
    (net (code "134") (name "Net-(T11-E)") (class "Default")
      (node (ref "R76") (pin "2") (pinfunction "2_2") (pintype "passive"))
      (node (ref "T11") (pin "2") (pinfunction "E_2") (pintype "passive"))
    )
    (net (code "135") (name "Net-(U1-AREF)") (class "Default")
      (node (ref "C14") (pin "1") (pinfunction "1_1") (pintype "passive"))
      (node (ref "U1") (pin "20") (pinfunction "AREF_20") (pintype "input"))
    )
    (net (code "136") (name "Net-(U1-PB6)") (class "Default")
      (node (ref "U1") (pin "7") (pinfunction "PB6_7") (pintype "bidirectional"))
      (node (ref "Y1") (pin "1") (pinfunction "1_1") (pintype "passive"))
    )
    (net (code "137") (name "Net-(U1-PB7)") (class "Default")
      (node (ref "U1") (pin "8") (pinfunction "PB7_8") (pintype "bidirectional"))
      (node (ref "Y1") (pin "3") (pinfunction "3_3") (pintype "passive"))
    )
    (net (code "138") (name "OA") (class "Default")
      (node (ref "MCP1") (pin "23") (pinfunction "GPA2_23") (pintype "bidirectional"))
      (node (ref "R23") (pin "1") (pinfunction "1_1") (pintype "passive"))
    )
    (net (code "139") (name "OB") (class "Default")
      (node (ref "MCP1") (pin "24") (pinfunction "GPA3_24") (pintype "bidirectional"))
      (node (ref "R24") (pin "1") (pinfunction "1_1") (pintype "passive"))
    )
    (net (code "140") (name "OC") (class "Default")
      (node (ref "MCP1") (pin "26") (pinfunction "GPA5_26") (pintype "bidirectional"))
      (node (ref "R26") (pin "1") (pinfunction "1_1") (pintype "passive"))
    )
    (net (code "141") (name "OD") (class "Default")
      (node (ref "MCP1") (pin "27") (pinfunction "GPA6_27") (pintype "bidirectional"))
      (node (ref "R27") (pin "1") (pinfunction "1_1") (pintype "passive"))
    )
    (net (code "142") (name "ODP") (class "Default")
      (node (ref "MCP1") (pin "25") (pinfunction "GPA4_25") (pintype "bidirectional"))
      (node (ref "R25") (pin "1") (pinfunction "1_1") (pintype "passive"))
    )
    (net (code "143") (name "OE") (class "Default")
      (node (ref "MCP1") (pin "28") (pinfunction "GPA7_28") (pintype "bidirectional"))
      (node (ref "R28") (pin "1") (pinfunction "1_1") (pintype "passive"))
    )
    (net (code "144") (name "OF") (class "Default")
      (node (ref "MCP1") (pin "22") (pinfunction "GPA1_22") (pintype "bidirectional"))
      (node (ref "R22") (pin "1") (pinfunction "1_1") (pintype "passive"))
    )
    (net (code "145") (name "OG") (class "Default")
      (node (ref "MCP1") (pin "21") (pinfunction "GPA0_21") (pintype "bidirectional"))
      (node (ref "R21") (pin "1") (pinfunction "1_1") (pintype "passive"))
    )
    (net (code "146") (name "RESET") (class "Default")
      (node (ref "ICSP") (pin "5") (pinfunction "5_5") (pintype "bidirectional"))
      (node (ref "R60") (pin "1") (pinfunction "1_1") (pintype "passive"))
      (node (ref "U1") (pin "29") (pinfunction "PC6_29") (pintype "bidirectional"))
    )
    (net (code "147") (name "RLBTLED") (class "Default")
      (node (ref "MCP2") (pin "3") (pinfunction "GPB2_3") (pintype "bidirectional"))
      (node (ref "R76") (pin "1") (pinfunction "1_1") (pintype "passive"))
    )
    (net (code "148") (name "RX") (class "Default")
      (node (ref "Q2") (pin "3") (pinfunction "D_3") (pintype "passive"))
      (node (ref "R68") (pin "1") (pinfunction "1_1") (pintype "passive"))
      (node (ref "U1") (pin "30") (pinfunction "PD0_30") (pintype "bidirectional"))
    )
    (net (code "149") (name "RXD") (class "Default")
      (node (ref "J2") (pin "10") (pinfunction "RXI_10") (pintype "input"))
      (node (ref "Q3") (pin "2") (pinfunction "S_2") (pintype "passive"))
      (node (ref "R66") (pin "1") (pinfunction "1_1") (pintype "passive"))
      (node (ref "RPI-CM4") (pin "51") (pinfunction "GPIO15_51") (pintype "passive"))
    )
    (net (code "150") (name "SCK") (class "Default")
      (node (ref "ICSP") (pin "3") (pinfunction "3_3") (pintype "bidirectional"))
      (node (ref "U1") (pin "17") (pinfunction "PB5_17") (pintype "bidirectional"))
    )
    (net (code "151") (name "SCL") (class "Default")
      (node (ref "MCP1") (pin "12") (pinfunction "SCK_12") (pintype "input"))
      (node (ref "MCP2") (pin "12") (pinfunction "SCK_12") (pintype "input"))
      (node (ref "R71") (pin "1") (pinfunction "1_1") (pintype "passive"))
      (node (ref "U1") (pin "28") (pinfunction "PC5_28") (pintype "bidirectional"))
    )
    (net (code "152") (name "SCLPI") (class "Default")
      (node (ref "J2") (pin "5") (pinfunction "SCL_5") (pintype "bidirectional"))
      (node (ref "RPI-CM4") (pin "80") (pinfunction "SCL0_80") (pintype "passive"))
    )
    (net (code "153") (name "SDA") (class "Default")
      (node (ref "MCP1") (pin "13") (pinfunction "SDA_13") (pintype "bidirectional"))
      (node (ref "MCP2") (pin "13") (pinfunction "SDA_13") (pintype "bidirectional"))
      (node (ref "R70") (pin "1") (pinfunction "1_1") (pintype "passive"))
      (node (ref "U1") (pin "27") (pinfunction "PC4_27") (pintype "bidirectional"))
    )
    (net (code "154") (name "SDAPI") (class "Default")
      (node (ref "J2") (pin "3") (pinfunction "SDA_3") (pintype "bidirectional"))
      (node (ref "RPI-CM4") (pin "82") (pinfunction "SDA0_82") (pintype "passive"))
    )
    (net (code "155") (name "TX") (class "Default")
      (node (ref "Q3") (pin "3") (pinfunction "D_3") (pintype "passive"))
      (node (ref "R69") (pin "1") (pinfunction "1_1") (pintype "passive"))
      (node (ref "U1") (pin "31") (pinfunction "PD1_31") (pintype "bidirectional"))
    )
    (net (code "156") (name "TXD") (class "Default")
      (node (ref "J2") (pin "8") (pinfunction "TXO_8") (pintype "output"))
      (node (ref "Q2") (pin "2") (pinfunction "S_2") (pintype "passive"))
      (node (ref "R65") (pin "1") (pinfunction "1_1") (pintype "passive"))
      (node (ref "RPI-CM4") (pin "55") (pinfunction "GPIO14_55") (pintype "passive"))
    )
    (net (code "157") (name "USB_N") (class "Default")
      (node (ref "D14") (pin "2") (pinfunction "D-_2") (pintype "bidirectional"))
      (node (ref "RPI-CM4") (pin "103") (pinfunction "USB_N_103") (pintype "passive"))
      (node (ref "USB0") (pin "D-") (pinfunction "D-_D-") (pintype "bidirectional"))
    )
    (net (code "158") (name "USB_P") (class "Default")
      (node (ref "D14") (pin "1") (pinfunction "D+_1") (pintype "bidirectional"))
      (node (ref "RPI-CM4") (pin "105") (pinfunction "USB_P_105") (pintype "passive"))
      (node (ref "USB0") (pin "D+") (pinfunction "D+_D+") (pintype "bidirectional"))
    )
    (net (code "159") (name "unconnected-(HDMI0-UTIL-PadP$14)") (class "Default")
      (node (ref "HDMI0") (pin "P$14") (pinfunction "UTIL_P$14") (pintype "bidirectional"))
    )
    (net (code "160") (name "unconnected-(IC1-~{FLT}-Pad3)") (class "Default")
      (node (ref "IC1") (pin "3") (pinfunction "~{FLT}_3") (pintype "bidirectional"))
    )
    (net (code "161") (name "unconnected-(MCP1-GPB0-Pad1)") (class "Default")
      (node (ref "MCP1") (pin "1") (pinfunction "GPB0_1") (pintype "bidirectional"))
    )
    (net (code "162") (name "unconnected-(MCP1-GPB1-Pad2)") (class "Default")
      (node (ref "MCP1") (pin "2") (pinfunction "GPB1_2") (pintype "bidirectional"))
    )
    (net (code "163") (name "unconnected-(MCP1-GPB2-Pad3)") (class "Default")
      (node (ref "MCP1") (pin "3") (pinfunction "GPB2_3") (pintype "bidirectional"))
    )
    (net (code "164") (name "unconnected-(MCP1-GPB3-Pad4)") (class "Default")
      (node (ref "MCP1") (pin "4") (pinfunction "GPB3_4") (pintype "bidirectional"))
    )
    (net (code "165") (name "unconnected-(MCP1-GPB4-Pad5)") (class "Default")
      (node (ref "MCP1") (pin "5") (pinfunction "GPB4_5") (pintype "bidirectional"))
    )
    (net (code "166") (name "unconnected-(MCP1-GPB5-Pad6)") (class "Default")
      (node (ref "MCP1") (pin "6") (pinfunction "GPB5_6") (pintype "bidirectional"))
    )
    (net (code "167") (name "unconnected-(MCP1-GPB6-Pad7)") (class "Default")
      (node (ref "MCP1") (pin "7") (pinfunction "GPB6_7") (pintype "bidirectional"))
    )
    (net (code "168") (name "unconnected-(MCP1-GPB7-Pad8)") (class "Default")
      (node (ref "MCP1") (pin "8") (pinfunction "GPB7_8") (pintype "bidirectional"))
    )
    (net (code "169") (name "unconnected-(MCP1-INTA-Pad20)") (class "Default")
      (node (ref "MCP1") (pin "20") (pinfunction "INTA_20") (pintype "output"))
    )
    (net (code "170") (name "unconnected-(MCP1-INTB-Pad19)") (class "Default")
      (node (ref "MCP1") (pin "19") (pinfunction "INTB_19") (pintype "output"))
    )
    (net (code "171") (name "unconnected-(MCP1-NC{slash}11-Pad11)") (class "Default")
      (node (ref "MCP1") (pin "11") (pinfunction "NC/11_11") (pintype "no_connect"))
    )
    (net (code "172") (name "unconnected-(MCP1-NC{slash}14-Pad14)") (class "Default")
      (node (ref "MCP1") (pin "14") (pinfunction "NC/14_14") (pintype "no_connect"))
    )
    (net (code "173") (name "unconnected-(MCP2-GPB3-Pad4)") (class "Default")
      (node (ref "MCP2") (pin "4") (pinfunction "GPB3_4") (pintype "bidirectional"))
    )
    (net (code "174") (name "unconnected-(MCP2-GPB4-Pad5)") (class "Default")
      (node (ref "MCP2") (pin "5") (pinfunction "GPB4_5") (pintype "bidirectional"))
    )
    (net (code "175") (name "unconnected-(MCP2-GPB5-Pad6)") (class "Default")
      (node (ref "MCP2") (pin "6") (pinfunction "GPB5_6") (pintype "bidirectional"))
    )
    (net (code "176") (name "unconnected-(MCP2-GPB6-Pad7)") (class "Default")
      (node (ref "MCP2") (pin "7") (pinfunction "GPB6_7") (pintype "bidirectional"))
    )
    (net (code "177") (name "unconnected-(MCP2-GPB7-Pad8)") (class "Default")
      (node (ref "MCP2") (pin "8") (pinfunction "GPB7_8") (pintype "bidirectional"))
    )
    (net (code "178") (name "unconnected-(MCP2-INTA-Pad20)") (class "Default")
      (node (ref "MCP2") (pin "20") (pinfunction "INTA_20") (pintype "output"))
    )
    (net (code "179") (name "unconnected-(MCP2-INTB-Pad19)") (class "Default")
      (node (ref "MCP2") (pin "19") (pinfunction "INTB_19") (pintype "output"))
    )
    (net (code "180") (name "unconnected-(MCP2-NC{slash}11-Pad11)") (class "Default")
      (node (ref "MCP2") (pin "11") (pinfunction "NC/11_11") (pintype "no_connect"))
    )
    (net (code "181") (name "unconnected-(MCP2-NC{slash}14-Pad14)") (class "Default")
      (node (ref "MCP2") (pin "14") (pinfunction "NC/14_14") (pintype "no_connect"))
    )
    (net (code "182") (name "unconnected-(RPI-CM4A-ANALOGP0-Pad96)") (class "Default")
      (node (ref "RPI-CM4") (pin "96") (pinfunction "ANALOGP0_96") (pintype "passive"))
    )
    (net (code "183") (name "unconnected-(RPI-CM4A-ANALOGP1-Pad94)") (class "Default")
      (node (ref "RPI-CM4") (pin "94") (pinfunction "ANALOGP1_94") (pintype "passive"))
    )
    (net (code "184") (name "unconnected-(RPI-CM4A-BT_~{DISABLE}-Pad91)") (class "Default")
      (node (ref "RPI-CM4") (pin "91") (pinfunction "BT_~{DISABLE}_91") (pintype "passive"))
    )
    (net (code "185") (name "unconnected-(RPI-CM4A-CAMERA_GPIO-Pad97)") (class "Default")
      (node (ref "RPI-CM4") (pin "97") (pinfunction "CAMERA_GPIO_97") (pintype "passive"))
    )
    (net (code "186") (name "unconnected-(RPI-CM4A-CM4_1.8V(OUTPUT)-Pad88)") (class "Default")
      (node (ref "RPI-CM4") (pin "88") (pinfunction "CM4_1.8V(OUTPUT)_88") (pintype "passive"))
    )
    (net (code "187") (name "unconnected-(RPI-CM4A-CM4_1.8V(OUTPUT)-Pad90)") (class "Default")
      (node (ref "RPI-CM4") (pin "90") (pinfunction "CM4_1.8V(OUTPUT)_90") (pintype "passive"))
    )
    (net (code "188") (name "unconnected-(RPI-CM4A-ETH_PAIR0_N-Pad10)") (class "Default")
      (node (ref "RPI-CM4") (pin "10") (pinfunction "ETH_PAIR0_N_10") (pintype "passive"))
    )
    (net (code "189") (name "unconnected-(RPI-CM4A-ETH_PAIR0_P-Pad12)") (class "Default")
      (node (ref "RPI-CM4") (pin "12") (pinfunction "ETH_PAIR0_P_12") (pintype "passive"))
    )
    (net (code "190") (name "unconnected-(RPI-CM4A-ETH_PAIR1_N-Pad6)") (class "Default")
      (node (ref "RPI-CM4") (pin "6") (pinfunction "ETH_PAIR1_N_6") (pintype "passive"))
    )
    (net (code "191") (name "unconnected-(RPI-CM4A-ETH_PAIR1_P-Pad4)") (class "Default")
      (node (ref "RPI-CM4") (pin "4") (pinfunction "ETH_PAIR1_P_4") (pintype "passive"))
    )
    (net (code "192") (name "unconnected-(RPI-CM4A-ETH_PAIR2_N-Pad9)") (class "Default")
      (node (ref "RPI-CM4") (pin "9") (pinfunction "ETH_PAIR2_N_9") (pintype "passive"))
    )
    (net (code "193") (name "unconnected-(RPI-CM4A-ETH_PAIR2_P-Pad11)") (class "Default")
      (node (ref "RPI-CM4") (pin "11") (pinfunction "ETH_PAIR2_P_11") (pintype "passive"))
    )
    (net (code "194") (name "unconnected-(RPI-CM4A-ETH_PAIR3_N-Pad5)") (class "Default")
      (node (ref "RPI-CM4") (pin "5") (pinfunction "ETH_PAIR3_N_5") (pintype "passive"))
    )
    (net (code "195") (name "unconnected-(RPI-CM4A-ETH_PAIR3_P-Pad3)") (class "Default")
      (node (ref "RPI-CM4") (pin "3") (pinfunction "ETH_PAIR3_P_3") (pintype "passive"))
    )
    (net (code "196") (name "unconnected-(RPI-CM4A-ETH_SYNC_IN-Pad16)") (class "Default")
      (node (ref "RPI-CM4") (pin "16") (pinfunction "ETH_SYNC_IN_16") (pintype "passive"))
    )
    (net (code "197") (name "unconnected-(RPI-CM4A-ETH_SYNC_OUT-Pad18)") (class "Default")
      (node (ref "RPI-CM4") (pin "18") (pinfunction "ETH_SYNC_OUT_18") (pintype "passive"))
    )
    (net (code "198") (name "unconnected-(RPI-CM4A-ETH_~{LED1}-Pad19)") (class "Default")
      (node (ref "RPI-CM4") (pin "19") (pinfunction "ETH_~{LED1}_19") (pintype "passive"))
    )
    (net (code "199") (name "unconnected-(RPI-CM4A-ETH_~{LED2}-Pad17)") (class "Default")
      (node (ref "RPI-CM4") (pin "17") (pinfunction "ETH_~{LED2}_17") (pintype "passive"))
    )
    (net (code "200") (name "unconnected-(RPI-CM4A-ETH_~{LED3}-Pad15)") (class "Default")
      (node (ref "RPI-CM4") (pin "15") (pinfunction "ETH_~{LED3}_15") (pintype "passive"))
    )
    (net (code "201") (name "unconnected-(RPI-CM4A-GLOBAL_EN-Pad99)") (class "Default")
      (node (ref "RPI-CM4") (pin "99") (pinfunction "GLOBAL_EN_99") (pintype "passive"))
    )
    (net (code "202") (name "unconnected-(RPI-CM4A-PI_LED_~{PWR}-Pad95)") (class "Default")
      (node (ref "RPI-CM4") (pin "95") (pinfunction "PI_LED_~{PWR}_95") (pintype "passive"))
    )
    (net (code "203") (name "unconnected-(RPI-CM4A-RESERVED-Pad76)") (class "Default")
      (node (ref "RPI-CM4") (pin "76") (pinfunction "RESERVED_76") (pintype "passive"))
    )
    (net (code "204") (name "unconnected-(RPI-CM4A-RUN_PG-Pad92)") (class "Default")
      (node (ref "RPI-CM4") (pin "92") (pinfunction "RUN_PG_92") (pintype "passive"))
    )
    (net (code "205") (name "unconnected-(RPI-CM4A-SD_CLK-Pad57)") (class "Default")
      (node (ref "RPI-CM4") (pin "57") (pinfunction "SD_CLK_57") (pintype "passive"))
    )
    (net (code "206") (name "unconnected-(RPI-CM4A-SD_CMD-Pad62)") (class "Default")
      (node (ref "RPI-CM4") (pin "62") (pinfunction "SD_CMD_62") (pintype "passive"))
    )
    (net (code "207") (name "unconnected-(RPI-CM4A-SD_DAT0-Pad63)") (class "Default")
      (node (ref "RPI-CM4") (pin "63") (pinfunction "SD_DAT0_63") (pintype "passive"))
    )
    (net (code "208") (name "unconnected-(RPI-CM4A-SD_DAT1-Pad67)") (class "Default")
      (node (ref "RPI-CM4") (pin "67") (pinfunction "SD_DAT1_67") (pintype "passive"))
    )
    (net (code "209") (name "unconnected-(RPI-CM4A-SD_DAT2-Pad69)") (class "Default")
      (node (ref "RPI-CM4") (pin "69") (pinfunction "SD_DAT2_69") (pintype "passive"))
    )
    (net (code "210") (name "unconnected-(RPI-CM4A-SD_DAT3-Pad61)") (class "Default")
      (node (ref "RPI-CM4") (pin "61") (pinfunction "SD_DAT3_61") (pintype "passive"))
    )
    (net (code "211") (name "unconnected-(RPI-CM4A-SD_DAT4-Pad68)") (class "Default")
      (node (ref "RPI-CM4") (pin "68") (pinfunction "SD_DAT4_68") (pintype "passive"))
    )
    (net (code "212") (name "unconnected-(RPI-CM4A-SD_DAT5-Pad64)") (class "Default")
      (node (ref "RPI-CM4") (pin "64") (pinfunction "SD_DAT5_64") (pintype "passive"))
    )
    (net (code "213") (name "unconnected-(RPI-CM4A-SD_DAT6-Pad72)") (class "Default")
      (node (ref "RPI-CM4") (pin "72") (pinfunction "SD_DAT6_72") (pintype "passive"))
    )
    (net (code "214") (name "unconnected-(RPI-CM4A-SD_DAT7-Pad70)") (class "Default")
      (node (ref "RPI-CM4") (pin "70") (pinfunction "SD_DAT7_70") (pintype "passive"))
    )
    (net (code "215") (name "unconnected-(RPI-CM4A-SD_PWR_ON-Pad75)") (class "Default")
      (node (ref "RPI-CM4") (pin "75") (pinfunction "SD_PWR_ON_75") (pintype "passive"))
    )
    (net (code "216") (name "unconnected-(RPI-CM4A-SD_VDD_OVERRIDE-Pad73)") (class "Default")
      (node (ref "RPI-CM4") (pin "73") (pinfunction "SD_VDD_OVERRIDE_73") (pintype "passive"))
    )
    (net (code "217") (name "unconnected-(RPI-CM4A-WL_~{DISABLE}-Pad89)") (class "Default")
      (node (ref "RPI-CM4") (pin "89") (pinfunction "WL_~{DISABLE}_89") (pintype "passive"))
    )
    (net (code "218") (name "unconnected-(RPI-CM4A-~{EXTRST}-Pad100)") (class "Default")
      (node (ref "RPI-CM4") (pin "100") (pinfunction "~{EXTRST}_100") (pintype "passive"))
    )
    (net (code "219") (name "unconnected-(RPI-CM4A-~{RPIBOOT}-Pad93)") (class "Default")
      (node (ref "RPI-CM4") (pin "93") (pinfunction "~{RPIBOOT}_93") (pintype "passive"))
    )
    (net (code "220") (name "unconnected-(RPI-CM4B-CAM0_C_N-Pad140)") (class "Default")
      (node (ref "RPI-CM4") (pin "140") (pinfunction "CAM0_C_N_140") (pintype "passive"))
    )
    (net (code "221") (name "unconnected-(RPI-CM4B-CAM0_C_P-Pad142)") (class "Default")
      (node (ref "RPI-CM4") (pin "142") (pinfunction "CAM0_C_P_142") (pintype "passive"))
    )
    (net (code "222") (name "unconnected-(RPI-CM4B-CAM0_D0_N-Pad128)") (class "Default")
      (node (ref "RPI-CM4") (pin "128") (pinfunction "CAM0_D0_N_128") (pintype "passive"))
    )
    (net (code "223") (name "unconnected-(RPI-CM4B-CAM0_D0_P-Pad130)") (class "Default")
      (node (ref "RPI-CM4") (pin "130") (pinfunction "CAM0_D0_P_130") (pintype "passive"))
    )
    (net (code "224") (name "unconnected-(RPI-CM4B-CAM0_D1_N-Pad134)") (class "Default")
      (node (ref "RPI-CM4") (pin "134") (pinfunction "CAM0_D1_N_134") (pintype "passive"))
    )
    (net (code "225") (name "unconnected-(RPI-CM4B-CAM0_D1_P-Pad136)") (class "Default")
      (node (ref "RPI-CM4") (pin "136") (pinfunction "CAM0_D1_P_136") (pintype "passive"))
    )
    (net (code "226") (name "unconnected-(RPI-CM4B-CAM1_C_N-Pad127)") (class "Default")
      (node (ref "RPI-CM4") (pin "127") (pinfunction "CAM1_C_N_127") (pintype "passive"))
    )
    (net (code "227") (name "unconnected-(RPI-CM4B-CAM1_C_P-Pad129)") (class "Default")
      (node (ref "RPI-CM4") (pin "129") (pinfunction "CAM1_C_P_129") (pintype "passive"))
    )
    (net (code "228") (name "unconnected-(RPI-CM4B-CAM1_D0_N-Pad115)") (class "Default")
      (node (ref "RPI-CM4") (pin "115") (pinfunction "CAM1_D0_N_115") (pintype "passive"))
    )
    (net (code "229") (name "unconnected-(RPI-CM4B-CAM1_D0_P-Pad117)") (class "Default")
      (node (ref "RPI-CM4") (pin "117") (pinfunction "CAM1_D0_P_117") (pintype "passive"))
    )
    (net (code "230") (name "unconnected-(RPI-CM4B-CAM1_D1_N-Pad121)") (class "Default")
      (node (ref "RPI-CM4") (pin "121") (pinfunction "CAM1_D1_N_121") (pintype "passive"))
    )
    (net (code "231") (name "unconnected-(RPI-CM4B-CAM1_D1_P-Pad123)") (class "Default")
      (node (ref "RPI-CM4") (pin "123") (pinfunction "CAM1_D1_P_123") (pintype "passive"))
    )
    (net (code "232") (name "unconnected-(RPI-CM4B-CAM1_D2_N-Pad133)") (class "Default")
      (node (ref "RPI-CM4") (pin "133") (pinfunction "CAM1_D2_N_133") (pintype "passive"))
    )
    (net (code "233") (name "unconnected-(RPI-CM4B-CAM1_D2_P-Pad135)") (class "Default")
      (node (ref "RPI-CM4") (pin "135") (pinfunction "CAM1_D2_P_135") (pintype "passive"))
    )
    (net (code "234") (name "unconnected-(RPI-CM4B-CAM1_D3_N-Pad139)") (class "Default")
      (node (ref "RPI-CM4") (pin "139") (pinfunction "CAM1_D3_N_139") (pintype "passive"))
    )
    (net (code "235") (name "unconnected-(RPI-CM4B-CAM1_D3_P-Pad141)") (class "Default")
      (node (ref "RPI-CM4") (pin "141") (pinfunction "CAM1_D3_P_141") (pintype "passive"))
    )
    (net (code "236") (name "unconnected-(RPI-CM4B-DSI0_C_N-Pad169)") (class "Default")
      (node (ref "RPI-CM4") (pin "169") (pinfunction "DSI0_C_N_169") (pintype "passive"))
    )
    (net (code "237") (name "unconnected-(RPI-CM4B-DSI0_C_P-Pad171)") (class "Default")
      (node (ref "RPI-CM4") (pin "171") (pinfunction "DSI0_C_P_171") (pintype "passive"))
    )
    (net (code "238") (name "unconnected-(RPI-CM4B-DSI0_D0_N-Pad157)") (class "Default")
      (node (ref "RPI-CM4") (pin "157") (pinfunction "DSI0_D0_N_157") (pintype "passive"))
    )
    (net (code "239") (name "unconnected-(RPI-CM4B-DSI0_D0_P-Pad159)") (class "Default")
      (node (ref "RPI-CM4") (pin "159") (pinfunction "DSI0_D0_P_159") (pintype "passive"))
    )
    (net (code "240") (name "unconnected-(RPI-CM4B-DSI0_D1_N-Pad163)") (class "Default")
      (node (ref "RPI-CM4") (pin "163") (pinfunction "DSI0_D1_N_163") (pintype "passive"))
    )
    (net (code "241") (name "unconnected-(RPI-CM4B-DSI0_D1_P-Pad165)") (class "Default")
      (node (ref "RPI-CM4") (pin "165") (pinfunction "DSI0_D1_P_165") (pintype "passive"))
    )
    (net (code "242") (name "unconnected-(RPI-CM4B-DSI1_C_N-Pad187)") (class "Default")
      (node (ref "RPI-CM4") (pin "187") (pinfunction "DSI1_C_N_187") (pintype "passive"))
    )
    (net (code "243") (name "unconnected-(RPI-CM4B-DSI1_C_P-Pad189)") (class "Default")
      (node (ref "RPI-CM4") (pin "189") (pinfunction "DSI1_C_P_189") (pintype "passive"))
    )
    (net (code "244") (name "unconnected-(RPI-CM4B-DSI1_D0_N-Pad175)") (class "Default")
      (node (ref "RPI-CM4") (pin "175") (pinfunction "DSI1_D0_N_175") (pintype "passive"))
    )
    (net (code "245") (name "unconnected-(RPI-CM4B-DSI1_D0_P-Pad177)") (class "Default")
      (node (ref "RPI-CM4") (pin "177") (pinfunction "DSI1_D0_P_177") (pintype "passive"))
    )
    (net (code "246") (name "unconnected-(RPI-CM4B-DSI1_D1_N-Pad181)") (class "Default")
      (node (ref "RPI-CM4") (pin "181") (pinfunction "DSI1_D1_N_181") (pintype "passive"))
    )
    (net (code "247") (name "unconnected-(RPI-CM4B-DSI1_D1_P-Pad183)") (class "Default")
      (node (ref "RPI-CM4") (pin "183") (pinfunction "DSI1_D1_P_183") (pintype "passive"))
    )
    (net (code "248") (name "unconnected-(RPI-CM4B-DSI1_D2_N-Pad193)") (class "Default")
      (node (ref "RPI-CM4") (pin "193") (pinfunction "DSI1_D2_N_193") (pintype "passive"))
    )
    (net (code "249") (name "unconnected-(RPI-CM4B-DSI1_D2_P-Pad195)") (class "Default")
      (node (ref "RPI-CM4") (pin "195") (pinfunction "DSI1_D2_P_195") (pintype "passive"))
    )
    (net (code "250") (name "unconnected-(RPI-CM4B-DSI1_D3_N-Pad194)") (class "Default")
      (node (ref "RPI-CM4") (pin "194") (pinfunction "DSI1_D3_N_194") (pintype "passive"))
    )
    (net (code "251") (name "unconnected-(RPI-CM4B-DSI1_D3_P-Pad196)") (class "Default")
      (node (ref "RPI-CM4") (pin "196") (pinfunction "DSI1_D3_P_196") (pintype "passive"))
    )
    (net (code "252") (name "unconnected-(RPI-CM4B-HDMI1_CEC-Pad149)") (class "Default")
      (node (ref "RPI-CM4") (pin "149") (pinfunction "HDMI1_CEC_149") (pintype "passive"))
    )
    (net (code "253") (name "unconnected-(RPI-CM4B-HDMI1_CLK_N-Pad166)") (class "Default")
      (node (ref "RPI-CM4") (pin "166") (pinfunction "HDMI1_CLK_N_166") (pintype "passive"))
    )
    (net (code "254") (name "unconnected-(RPI-CM4B-HDMI1_CLK_P-Pad164)") (class "Default")
      (node (ref "RPI-CM4") (pin "164") (pinfunction "HDMI1_CLK_P_164") (pintype "passive"))
    )
    (net (code "255") (name "unconnected-(RPI-CM4B-HDMI1_HOTPLUG-Pad143)") (class "Default")
      (node (ref "RPI-CM4") (pin "143") (pinfunction "HDMI1_HOTPLUG_143") (pintype "passive"))
    )
    (net (code "256") (name "unconnected-(RPI-CM4B-HDMI1_SCL-Pad147)") (class "Default")
      (node (ref "RPI-CM4") (pin "147") (pinfunction "HDMI1_SCL_147") (pintype "passive"))
    )
    (net (code "257") (name "unconnected-(RPI-CM4B-HDMI1_SDA-Pad145)") (class "Default")
      (node (ref "RPI-CM4") (pin "145") (pinfunction "HDMI1_SDA_145") (pintype "passive"))
    )
    (net (code "258") (name "unconnected-(RPI-CM4B-HDMI1_TX0_N-Pad160)") (class "Default")
      (node (ref "RPI-CM4") (pin "160") (pinfunction "HDMI1_TX0_N_160") (pintype "passive"))
    )
    (net (code "259") (name "unconnected-(RPI-CM4B-HDMI1_TX0_P-Pad158)") (class "Default")
      (node (ref "RPI-CM4") (pin "158") (pinfunction "HDMI1_TX0_P_158") (pintype "passive"))
    )
    (net (code "260") (name "unconnected-(RPI-CM4B-HDMI1_TX1_N-Pad154)") (class "Default")
      (node (ref "RPI-CM4") (pin "154") (pinfunction "HDMI1_TX1_N_154") (pintype "passive"))
    )
    (net (code "261") (name "unconnected-(RPI-CM4B-HDMI1_TX1_P-Pad152)") (class "Default")
      (node (ref "RPI-CM4") (pin "152") (pinfunction "HDMI1_TX1_P_152") (pintype "passive"))
    )
    (net (code "262") (name "unconnected-(RPI-CM4B-HDMI1_TX2_N-Pad148)") (class "Default")
      (node (ref "RPI-CM4") (pin "148") (pinfunction "HDMI1_TX2_N_148") (pintype "passive"))
    )
    (net (code "263") (name "unconnected-(RPI-CM4B-HDMI1_TX2_P-Pad146)") (class "Default")
      (node (ref "RPI-CM4") (pin "146") (pinfunction "HDMI1_TX2_P_146") (pintype "passive"))
    )
    (net (code "264") (name "unconnected-(RPI-CM4B-PCIE_CLK_N-Pad112)") (class "Default")
      (node (ref "RPI-CM4") (pin "112") (pinfunction "PCIE_CLK_N_112") (pintype "passive"))
    )
    (net (code "265") (name "unconnected-(RPI-CM4B-PCIE_CLK_P-Pad110)") (class "Default")
      (node (ref "RPI-CM4") (pin "110") (pinfunction "PCIE_CLK_P_110") (pintype "passive"))
    )
    (net (code "266") (name "unconnected-(RPI-CM4B-PCIE_CLK_~{REQ}-Pad102)") (class "Default")
      (node (ref "RPI-CM4") (pin "102") (pinfunction "PCIE_CLK_~{REQ}_102") (pintype "passive"))
    )
    (net (code "267") (name "unconnected-(RPI-CM4B-PCIE_RX_N-Pad118)") (class "Default")
      (node (ref "RPI-CM4") (pin "118") (pinfunction "PCIE_RX_N_118") (pintype "passive"))
    )
    (net (code "268") (name "unconnected-(RPI-CM4B-PCIE_RX_P-Pad116)") (class "Default")
      (node (ref "RPI-CM4") (pin "116") (pinfunction "PCIE_RX_P_116") (pintype "passive"))
    )
    (net (code "269") (name "unconnected-(RPI-CM4B-PCIE_TX_N-Pad124)") (class "Default")
      (node (ref "RPI-CM4") (pin "124") (pinfunction "PCIE_TX_N_124") (pintype "passive"))
    )
    (net (code "270") (name "unconnected-(RPI-CM4B-PCIE_TX_P-Pad122)") (class "Default")
      (node (ref "RPI-CM4") (pin "122") (pinfunction "PCIE_TX_P_122") (pintype "passive"))
    )
    (net (code "271") (name "unconnected-(RPI-CM4B-PCIE_~{RST}-Pad109)") (class "Default")
      (node (ref "RPI-CM4") (pin "109") (pinfunction "PCIE_~{RST}_109") (pintype "passive"))
    )
    (net (code "272") (name "unconnected-(RPI-CM4B-RESERVED-Pad104)") (class "Default")
      (node (ref "RPI-CM4") (pin "104") (pinfunction "RESERVED_104") (pintype "passive"))
    )
    (net (code "273") (name "unconnected-(RPI-CM4B-RESERVED-Pad106)") (class "Default")
      (node (ref "RPI-CM4") (pin "106") (pinfunction "RESERVED_106") (pintype "passive"))
    )
    (net (code "274") (name "unconnected-(RPI-CM4B-VDAC_COMP-Pad111)") (class "Default")
      (node (ref "RPI-CM4") (pin "111") (pinfunction "VDAC_COMP_111") (pintype "passive"))
    )
    (net (code "275") (name "unconnected-(U1-ADC6-Pad19)") (class "Default")
      (node (ref "U1") (pin "19") (pinfunction "ADC6_19") (pintype "input"))
    )
    (net (code "276") (name "unconnected-(U1-ADC7-Pad22)") (class "Default")
      (node (ref "U1") (pin "22") (pinfunction "ADC7_22") (pintype "input"))
    )
  )
)
